# Dashboard_rev5.net
KiCad netlist of a schematic drawn in EAGLE
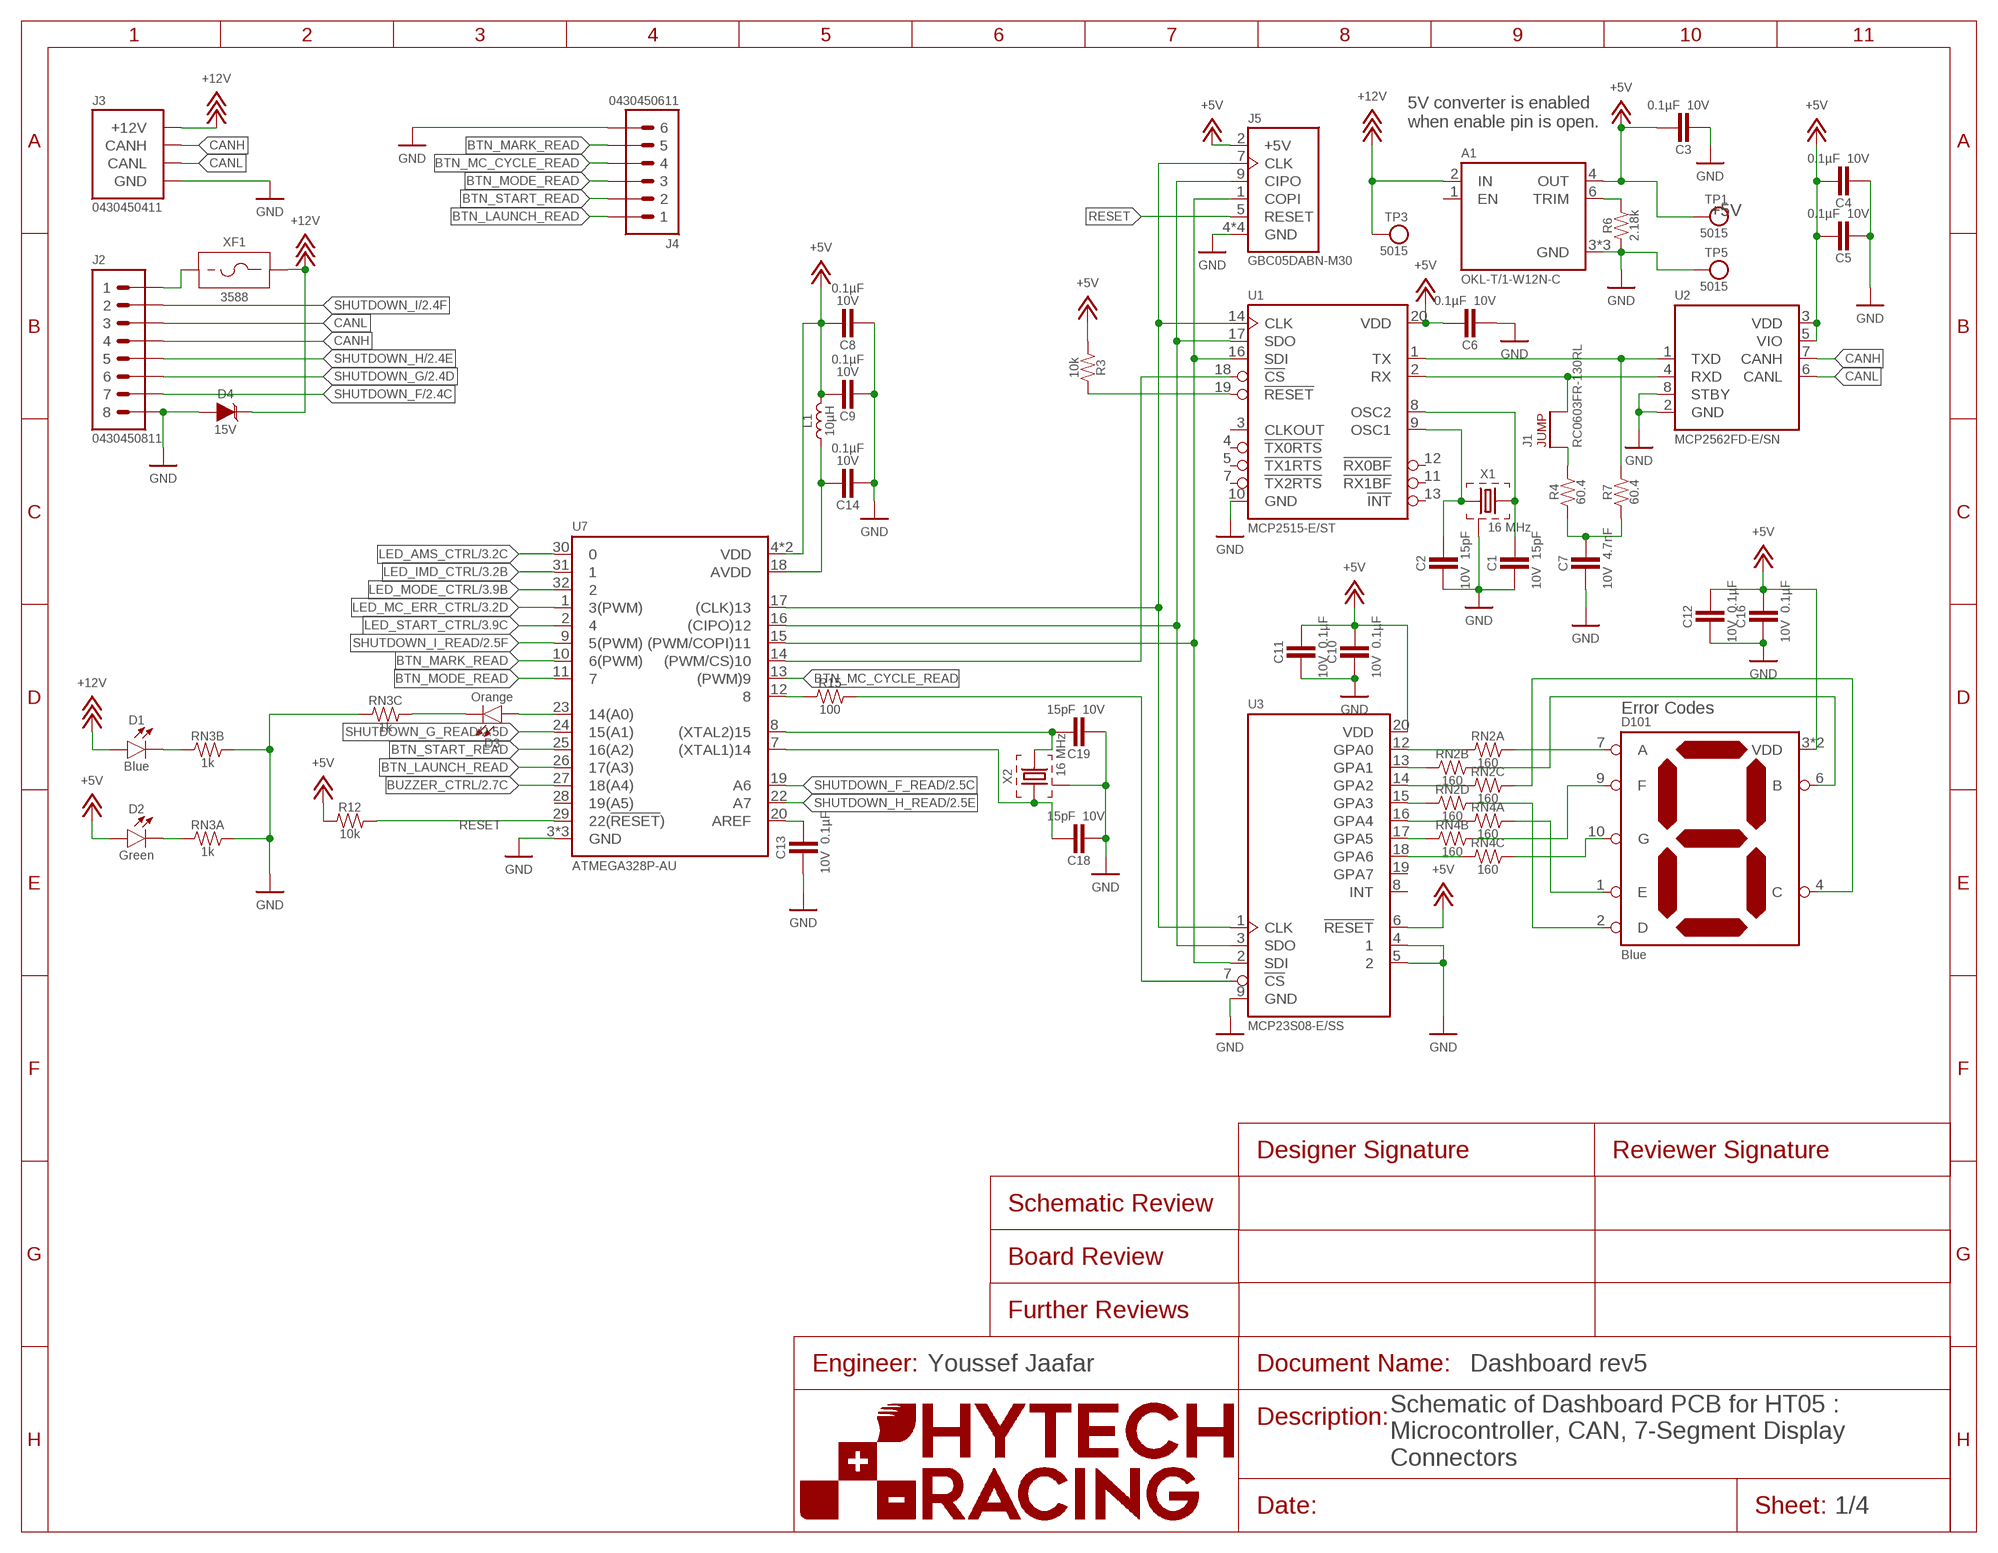
[diagram p0: schematic, sheet 1]
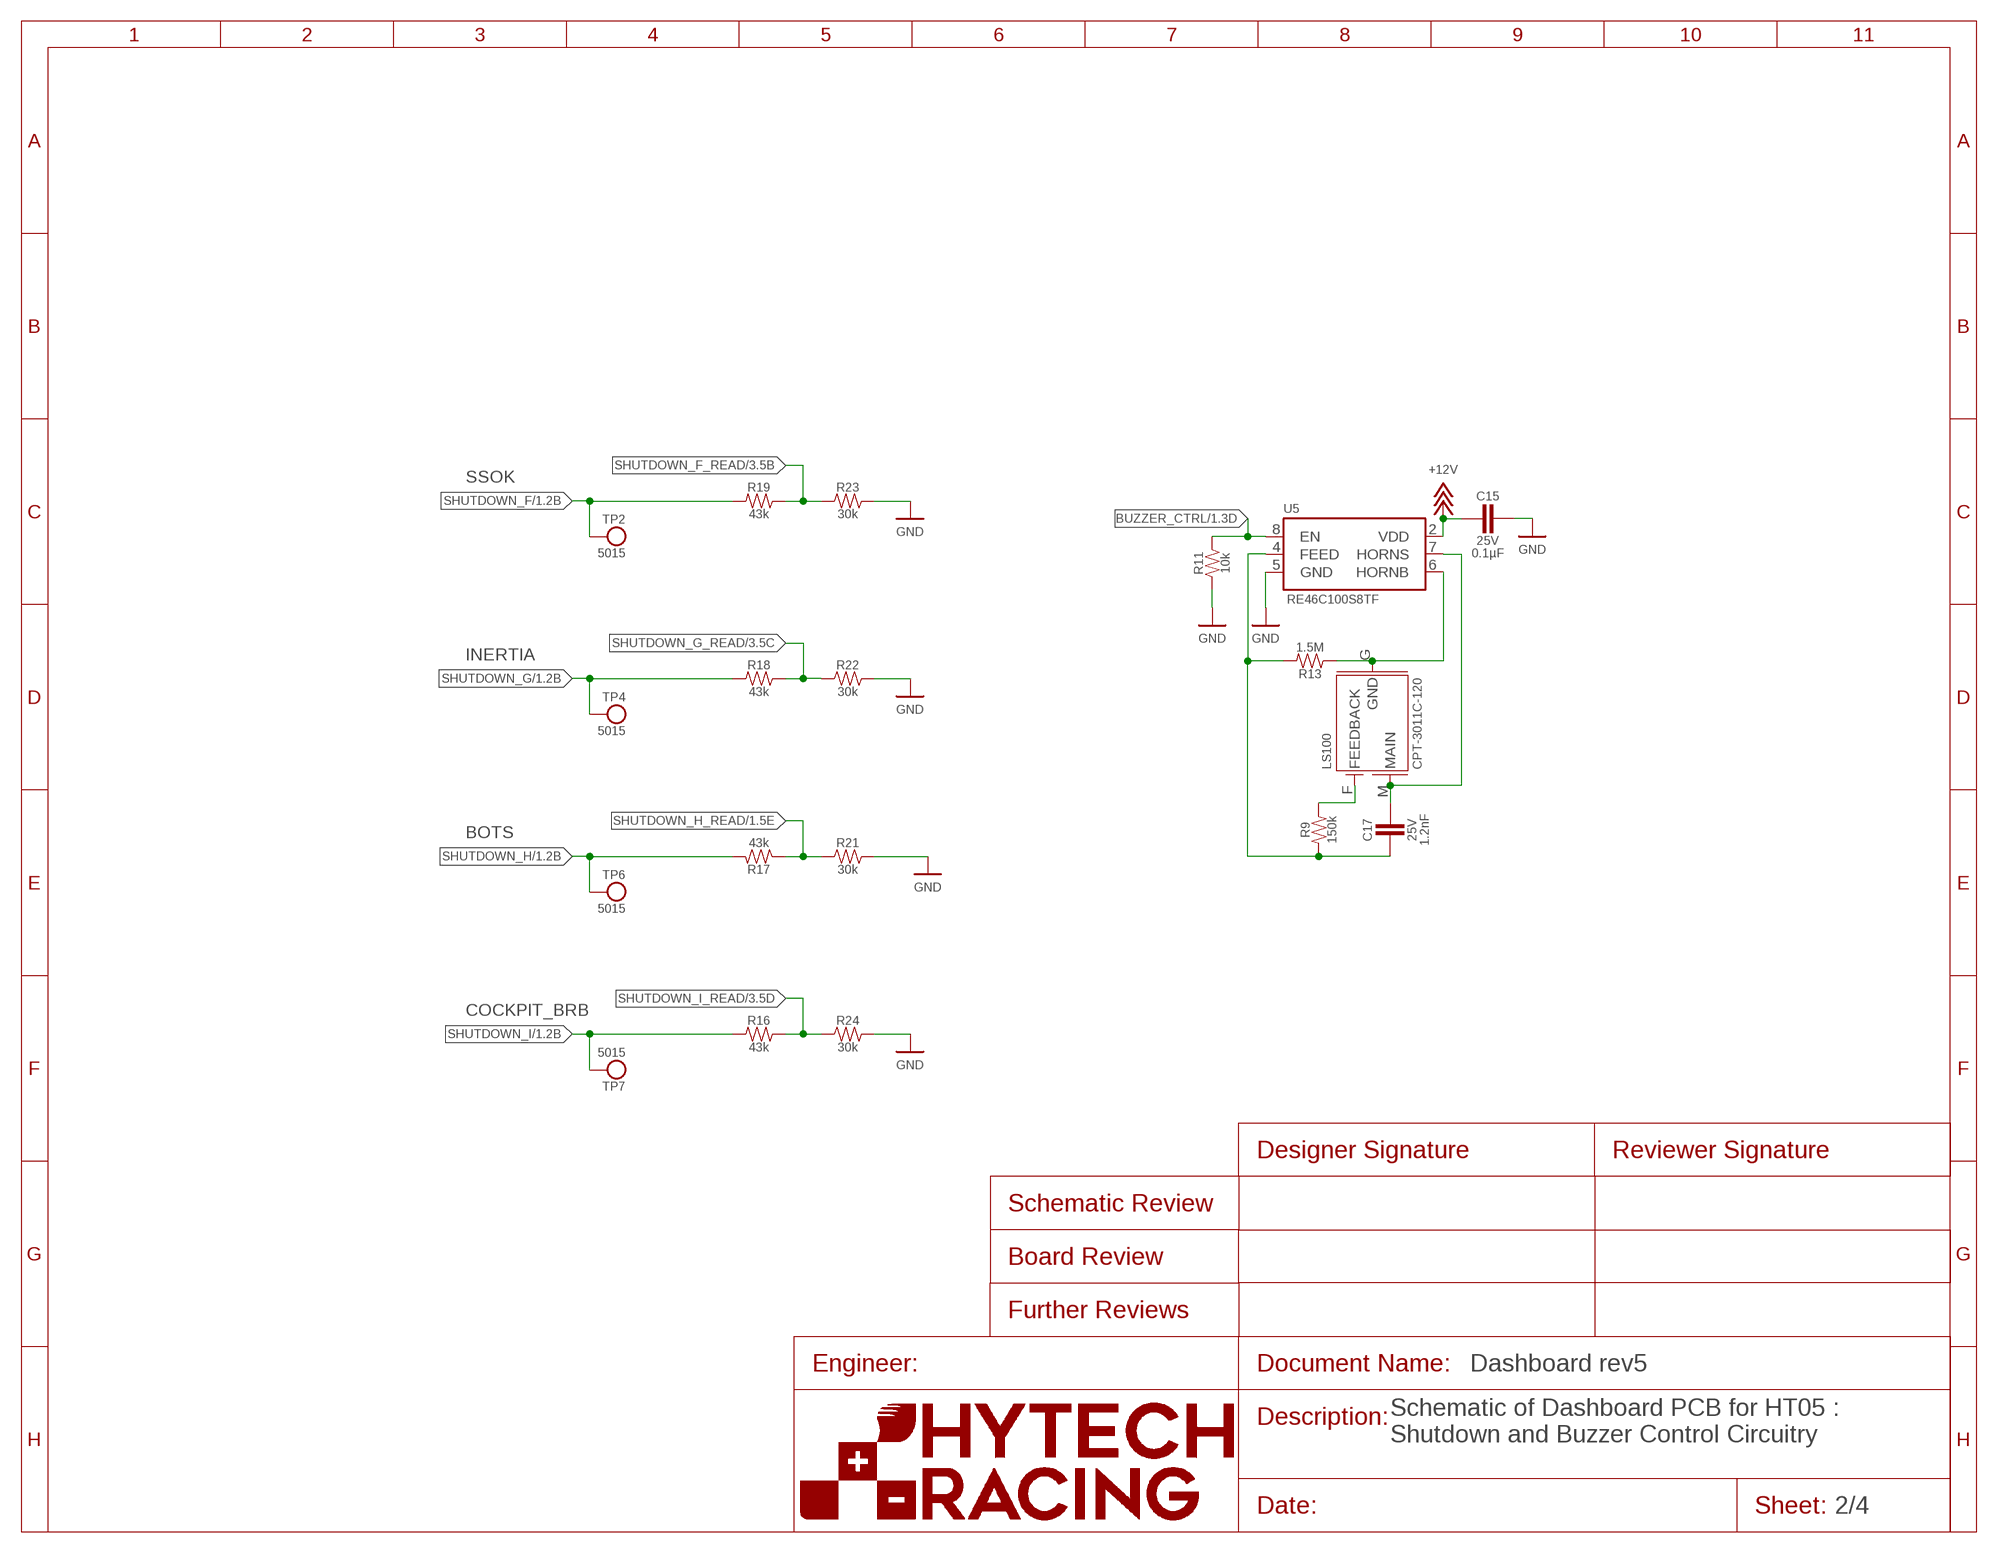
[diagram p1: schematic, sheet 2]
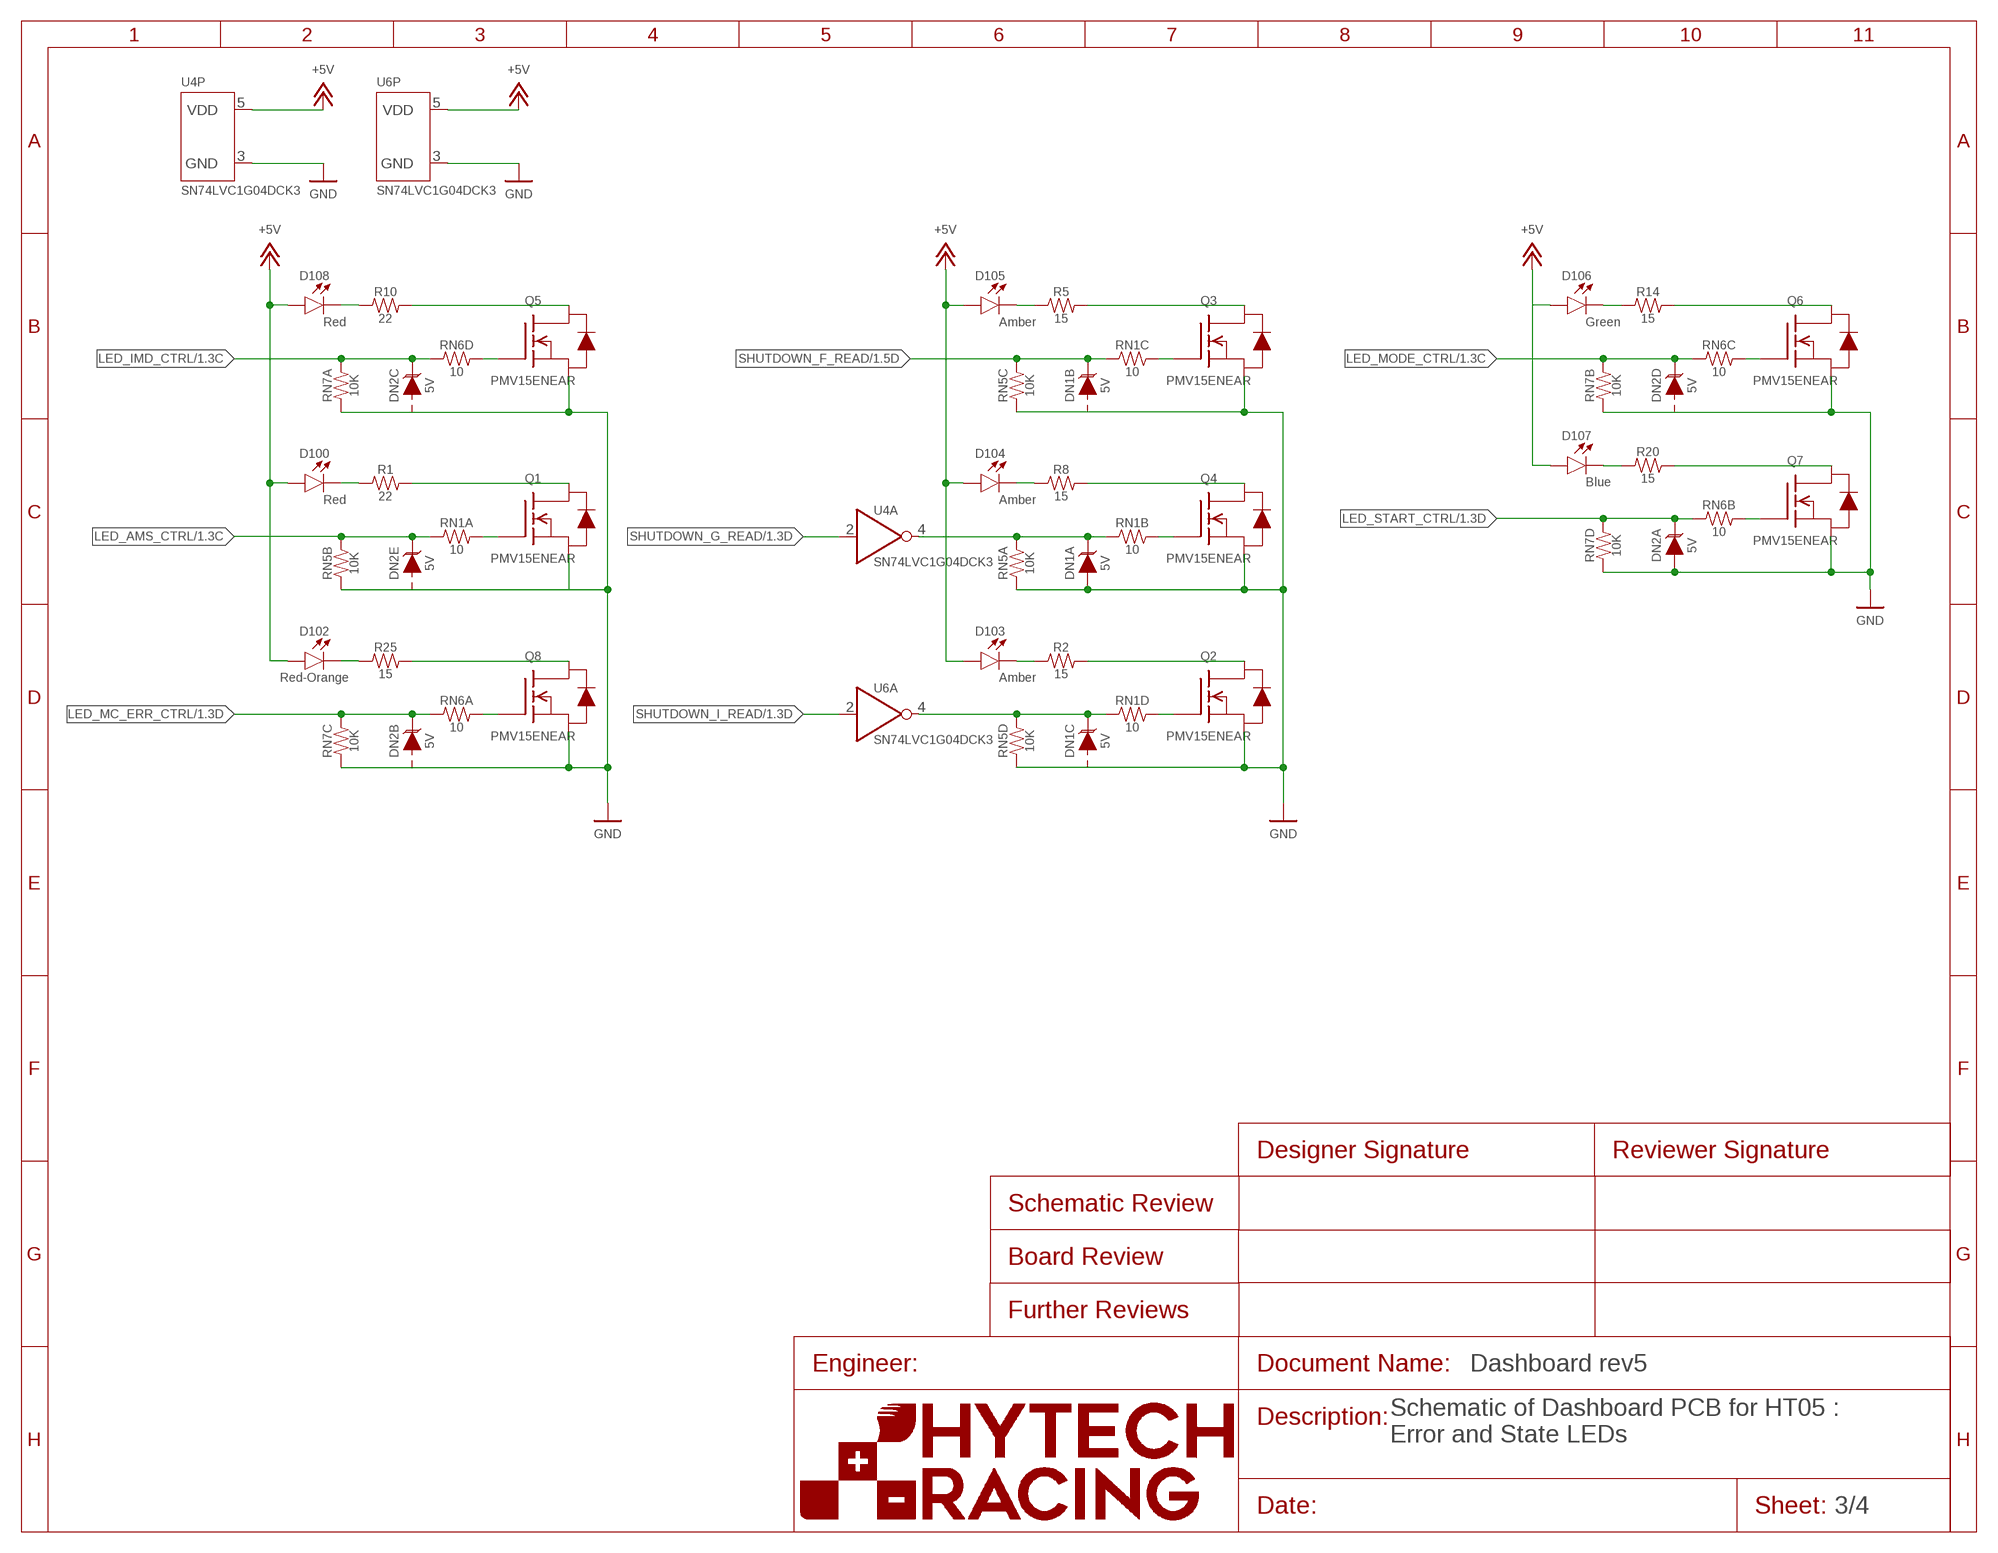
[diagram p2: schematic, sheet 3]
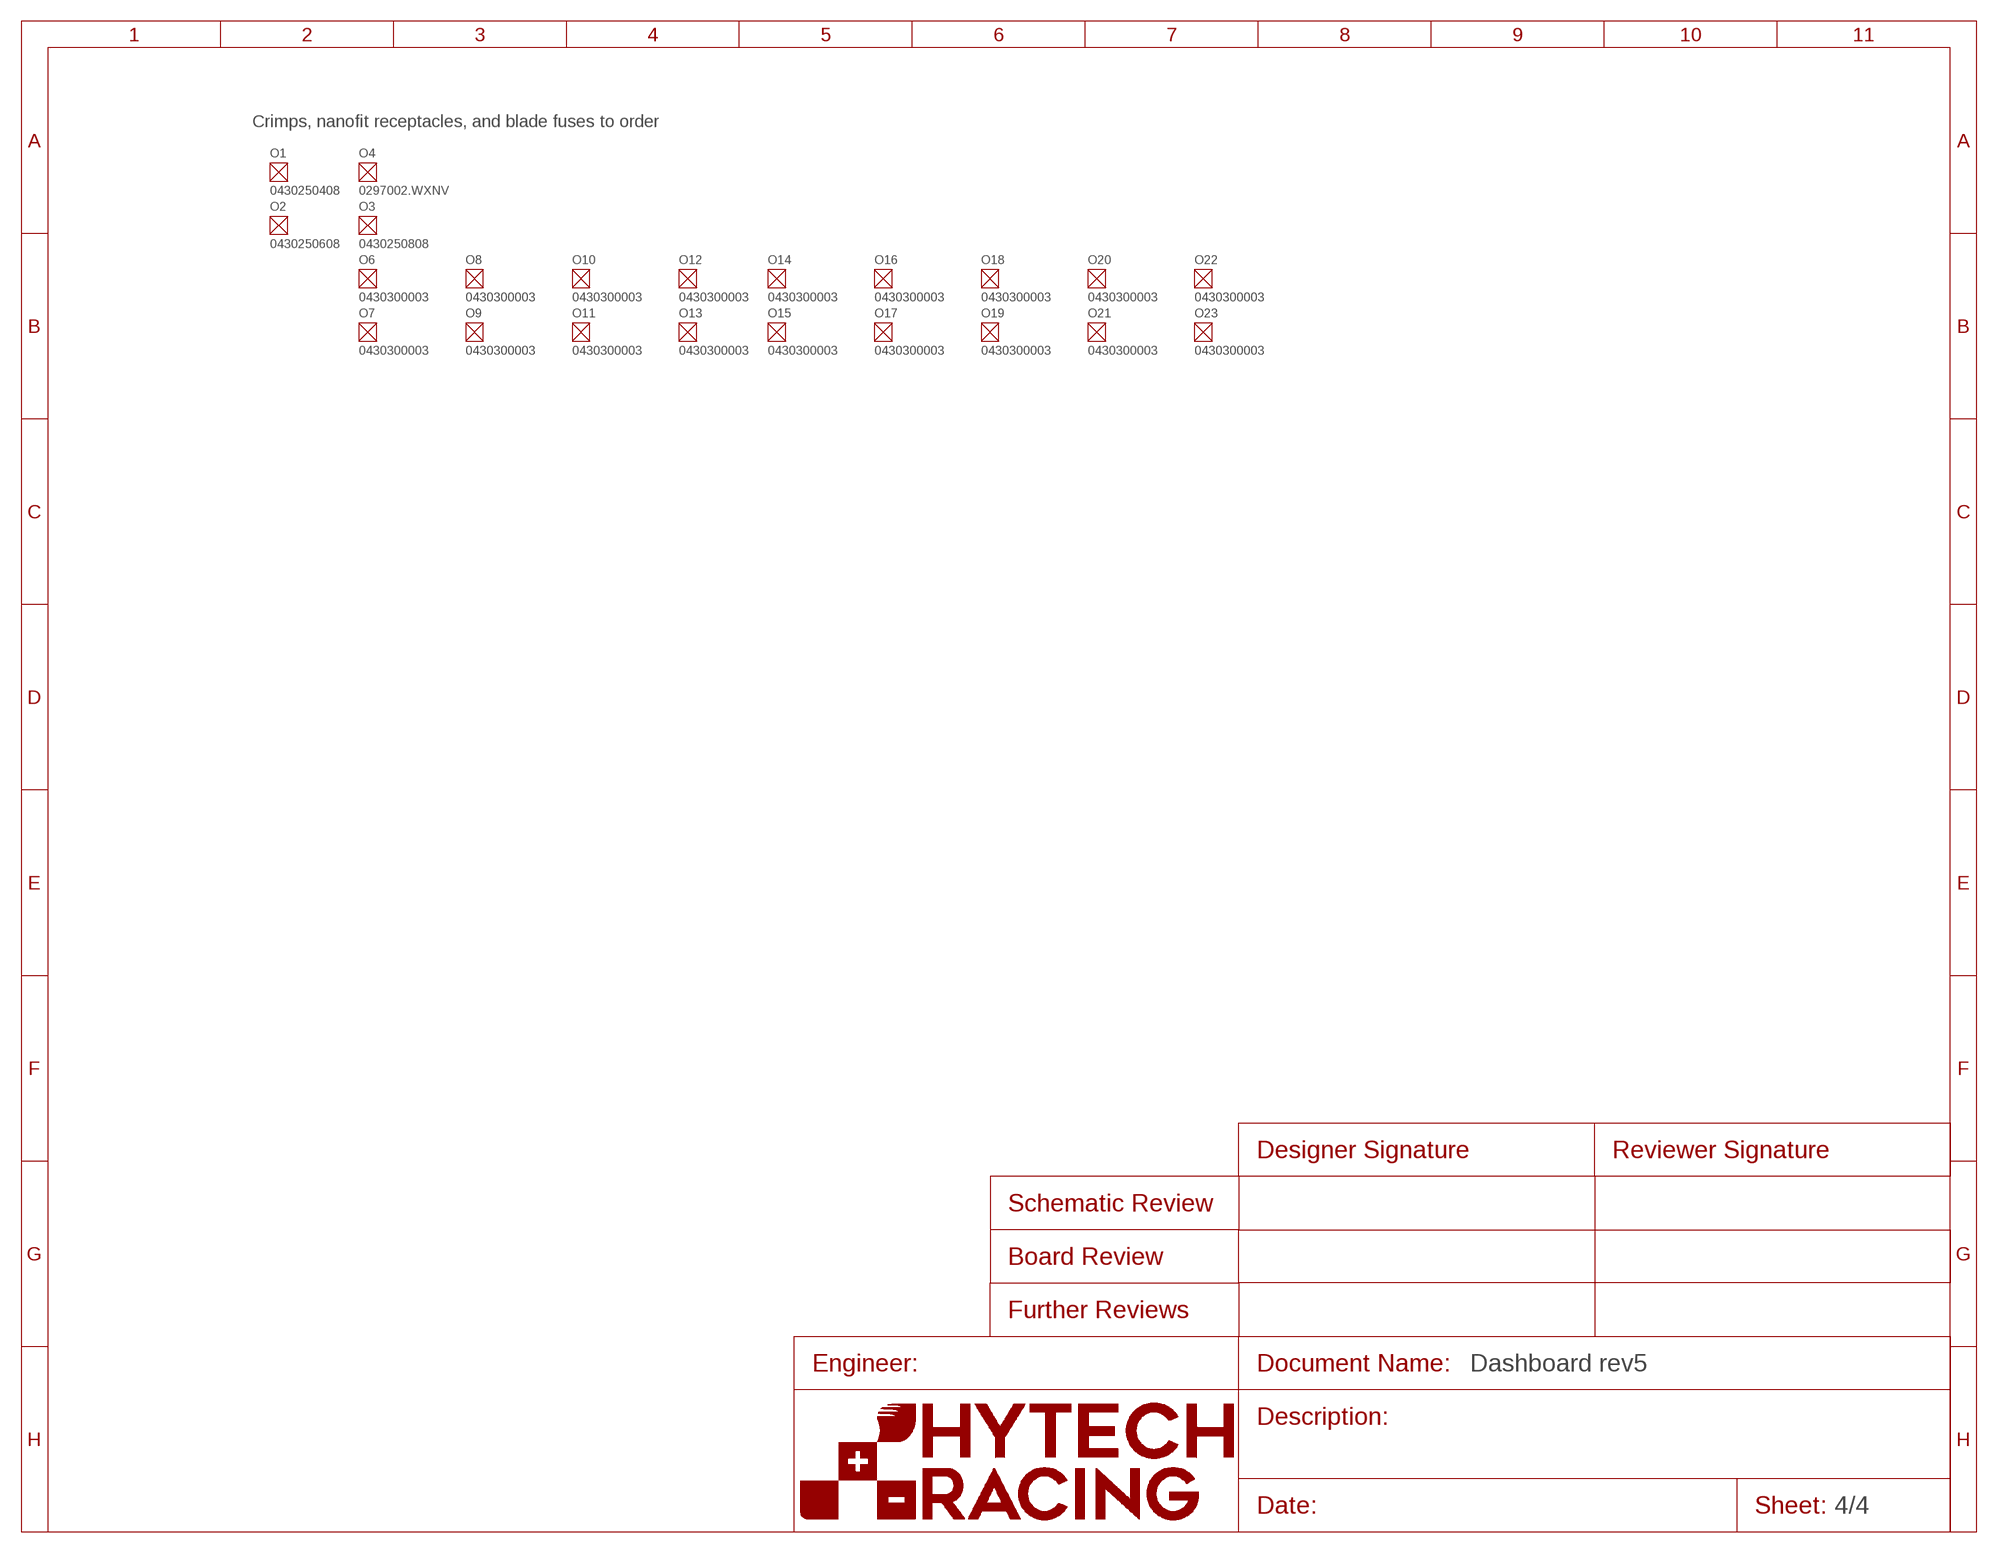
[diagram p3: schematic, sheet 4]

(export (version "E")
  (design (tool "Eeschema 10.0.6"))
  (components
    (comp (ref "D100")
      (value "LED_2835_RED")
      (footprint "eagle-import:2835-LED")
      (fields
        (field (name "COLOR") "Red")
        (field (name "MANUFACTURER") "Lumileds")
        (field (name "MPN") "L128-RED1003500000")
      )
      (libsource (lib "eagle-import") (part "LED_?_2835RED"))
    )
    (comp (ref "D102")
      (value "LED_2835_RED-ORANGE")
      (footprint "eagle-import:2835-LED")
      (fields
        (field (name "COLOR") "Red-Orange")
        (field (name "MANUFACTURER") "Lumileds")
        (field (name "MPN") "L128-RNG1003500000 ")
      )
      (libsource (lib "eagle-import") (part "LED_?_2835RED-ORANGE"))
    )
    (comp (ref "D103")
      (value "LED_2835_AMBER")
      (footprint "eagle-import:2835-LED")
      (fields
        (field (name "COLOR") "Amber")
        (field (name "MANUFACTURER") "Lumileds")
        (field (name "MPN") "L128-PCA1003500000")
      )
      (libsource (lib "eagle-import") (part "LED_?_2835AMBER"))
    )
    (comp (ref "D104")
      (value "LED_2835_AMBER")
      (footprint "eagle-import:2835-LED")
      (fields
        (field (name "COLOR") "Amber")
        (field (name "MANUFACTURER") "Lumileds")
        (field (name "MPN") "L128-PCA1003500000")
      )
      (libsource (lib "eagle-import") (part "LED_?_2835AMBER"))
    )
    (comp (ref "D105")
      (value "LED_2835_AMBER")
      (footprint "eagle-import:2835-LED")
      (fields
        (field (name "COLOR") "Amber")
        (field (name "MANUFACTURER") "Lumileds")
        (field (name "MPN") "L128-PCA1003500000")
      )
      (libsource (lib "eagle-import") (part "LED_?_2835AMBER"))
    )
    (comp (ref "D106")
      (value "LED_2835_GREEN")
      (footprint "eagle-import:2835-LED")
      (fields
        (field (name "COLOR") "Green")
        (field (name "MANUFACTURER") "Lumileds")
        (field (name "MPN") "L128-GRN1003500000")
      )
      (libsource (lib "eagle-import") (part "LED_?_2835GREEN"))
    )
    (comp (ref "D107")
      (value "LED_2835_BLUE")
      (footprint "eagle-import:2835-LED")
      (fields
        (field (name "COLOR") "Blue")
        (field (name "MANUFACTURER") "Lumileds")
        (field (name "MPN") "L128-BLU1003500000")
      )
      (libsource (lib "eagle-import") (part "LED_?_2835BLUE"))
    )
    (comp (ref "D108")
      (value "LED_2835_RED")
      (footprint "eagle-import:2835-LED")
      (fields
        (field (name "COLOR") "Red")
        (field (name "MANUFACTURER") "Lumileds")
        (field (name "MPN") "L128-RED1003500000")
      )
      (libsource (lib "eagle-import") (part "LED_?_2835RED"))
    )
    (comp (ref "DN1")
      (value "TVS_ARRAY_5V")
      (footprint "eagle-import:SOT-363")
      (fields
        (field (name "MANUFACTURER") "Vishay General Semiconductor - Diodes Division")
        (field (name "MPN") "VESD05A5-06G-G3-08")
        (field (name "VOLTAGE") "5V")
      )
      (libsource (lib "eagle-import") (part "TVS_ARRAY_5V"))
    )
    (comp (ref "DN2")
      (value "TVS_ARRAY_5V")
      (footprint "eagle-import:SOT-363")
      (fields
        (field (name "MANUFACTURER") "Vishay General Semiconductor - Diodes Division")
        (field (name "MPN") "VESD05A5-06G-G3-08")
        (field (name "VOLTAGE") "5V")
      )
      (libsource (lib "eagle-import") (part "TVS_ARRAY_5V"))
    )
    (comp (ref "Q1")
      (value "TRANSISTOR_N_MOS__PMV15ENEA")
      (footprint "eagle-import:SOT-23")
      (fields (field (name "MANUFACTURER") "Nexperia USA Inc.") (field (name "MPN") "PMV15ENEAR"))
      (libsource (lib "eagle-import") (part "TRANSISTOR_N_MOS_?_PMV15ENEA"))
    )
    (comp (ref "Q2")
      (value "TRANSISTOR_N_MOS__PMV15ENEA")
      (footprint "eagle-import:SOT-23")
      (fields (field (name "MANUFACTURER") "Nexperia USA Inc.") (field (name "MPN") "PMV15ENEAR"))
      (libsource (lib "eagle-import") (part "TRANSISTOR_N_MOS_?_PMV15ENEA"))
    )
    (comp (ref "Q3")
      (value "TRANSISTOR_N_MOS__PMV15ENEA")
      (footprint "eagle-import:SOT-23")
      (fields (field (name "MANUFACTURER") "Nexperia USA Inc.") (field (name "MPN") "PMV15ENEAR"))
      (libsource (lib "eagle-import") (part "TRANSISTOR_N_MOS_?_PMV15ENEA"))
    )
    (comp (ref "Q4")
      (value "TRANSISTOR_N_MOS__PMV15ENEA")
      (footprint "eagle-import:SOT-23")
      (fields (field (name "MANUFACTURER") "Nexperia USA Inc.") (field (name "MPN") "PMV15ENEAR"))
      (libsource (lib "eagle-import") (part "TRANSISTOR_N_MOS_?_PMV15ENEA"))
    )
    (comp (ref "Q5")
      (value "TRANSISTOR_N_MOS__PMV15ENEA")
      (footprint "eagle-import:SOT-23")
      (fields (field (name "MANUFACTURER") "Nexperia USA Inc.") (field (name "MPN") "PMV15ENEAR"))
      (libsource (lib "eagle-import") (part "TRANSISTOR_N_MOS_?_PMV15ENEA"))
    )
    (comp (ref "Q6")
      (value "TRANSISTOR_N_MOS__PMV15ENEA")
      (footprint "eagle-import:SOT-23")
      (fields (field (name "MANUFACTURER") "Nexperia USA Inc.") (field (name "MPN") "PMV15ENEAR"))
      (libsource (lib "eagle-import") (part "TRANSISTOR_N_MOS_?_PMV15ENEA"))
    )
    (comp (ref "Q7")
      (value "TRANSISTOR_N_MOS__PMV15ENEA")
      (footprint "eagle-import:SOT-23")
      (fields (field (name "MANUFACTURER") "Nexperia USA Inc.") (field (name "MPN") "PMV15ENEAR"))
      (libsource (lib "eagle-import") (part "TRANSISTOR_N_MOS_?_PMV15ENEA"))
    )
    (comp (ref "Q8")
      (value "TRANSISTOR_N_MOS__PMV15ENEA")
      (footprint "eagle-import:SOT-23")
      (fields (field (name "MANUFACTURER") "Nexperia USA Inc.") (field (name "MPN") "PMV15ENEAR"))
      (libsource (lib "eagle-import") (part "TRANSISTOR_N_MOS_?_PMV15ENEA"))
    )
    (comp (ref "R1")
      (value "RESISTOR_0805_22")
      (footprint "eagle-import:0805-RES")
      (fields
        (field (name "MANUFACTURER") "Panasonic Electronic Components")
        (field (name "MPN") "ERJ-P06F22R0V")
        (field (name "POWER") "0.5W")
        (field (name "RESISTANCE") "22")
      )
      (libsource (lib "eagle-import") (part "RESISTOR_?_080522"))
    )
    (comp (ref "R2")
      (value "RESISTOR_0603_15")
      (footprint "eagle-import:0603-RES")
      (fields
        (field (name "MANUFACTURER") "Vishay Dale")
        (field (name "MPN") "CRCW060315R0FKEAHP")
        (field (name "POWER") "0.33W")
        (field (name "RESISTANCE") "15")
      )
      (libsource (lib "eagle-import") (part "RESISTOR_?_060315"))
    )
    (comp (ref "R5")
      (value "RESISTOR_0603_15")
      (footprint "eagle-import:0603-RES")
      (fields
        (field (name "MANUFACTURER") "Vishay Dale")
        (field (name "MPN") "CRCW060315R0FKEAHP")
        (field (name "POWER") "0.33W")
        (field (name "RESISTANCE") "15")
      )
      (libsource (lib "eagle-import") (part "RESISTOR_?_060315"))
    )
    (comp (ref "R8")
      (value "RESISTOR_0603_15")
      (footprint "eagle-import:0603-RES")
      (fields
        (field (name "MANUFACTURER") "Vishay Dale")
        (field (name "MPN") "CRCW060315R0FKEAHP")
        (field (name "POWER") "0.33W")
        (field (name "RESISTANCE") "15")
      )
      (libsource (lib "eagle-import") (part "RESISTOR_?_060315"))
    )
    (comp (ref "R10")
      (value "RESISTOR_0805_22")
      (footprint "eagle-import:0805-RES")
      (fields
        (field (name "MANUFACTURER") "Panasonic Electronic Components")
        (field (name "MPN") "ERJ-P06F22R0V")
        (field (name "POWER") "0.5W")
        (field (name "RESISTANCE") "22")
      )
      (libsource (lib "eagle-import") (part "RESISTOR_?_080522"))
    )
    (comp (ref "R14")
      (value "RESISTOR_0603_15")
      (footprint "eagle-import:0603-RES")
      (fields
        (field (name "MANUFACTURER") "Vishay Dale")
        (field (name "MPN") "CRCW060315R0FKEAHP")
        (field (name "POWER") "0.33W")
        (field (name "RESISTANCE") "15")
      )
      (libsource (lib "eagle-import") (part "RESISTOR_?_060315"))
    )
    (comp (ref "R20")
      (value "RESISTOR_0603_15")
      (footprint "eagle-import:0603-RES")
      (fields
        (field (name "MANUFACTURER") "Vishay Dale")
        (field (name "MPN") "CRCW060315R0FKEAHP")
        (field (name "POWER") "0.33W")
        (field (name "RESISTANCE") "15")
      )
      (libsource (lib "eagle-import") (part "RESISTOR_?_060315"))
    )
    (comp (ref "R25")
      (value "RESISTOR_0603_15")
      (footprint "eagle-import:0603-RES")
      (fields
        (field (name "MANUFACTURER") "Vishay Dale")
        (field (name "MPN") "CRCW060315R0FKEAHP")
        (field (name "POWER") "0.33W")
        (field (name "RESISTANCE") "15")
      )
      (libsource (lib "eagle-import") (part "RESISTOR_?_060315"))
    )
    (comp (ref "RN1")
      (value "RESISTOR_NETWORK_4_10")
      (footprint "eagle-import:1206-RES-ARRAY")
      (fields
        (field (name "MANUFACTURER") "Bourns Inc.")
        (field (name "MPN") "CAT16-100J4LF")
        (field (name "POWER") "1/16W")
        (field (name "RESISTANCE") "10")
      )
      (libsource (lib "eagle-import") (part "RESISTOR_NETWORK_4_10"))
    )
    (comp (ref "RN5")
      (value "RESISTOR_NETWORK_4_10K")
      (footprint "eagle-import:1206-RES-ARRAY")
      (fields
        (field (name "MANUFACTURER") "Yageo")
        (field (name "MPN") "TC164-FR-0710KL")
        (field (name "POWER") "1/16W")
        (field (name "RESISTANCE") "10K")
      )
      (libsource (lib "eagle-import") (part "RESISTOR_NETWORK_4_10K"))
    )
    (comp (ref "RN6")
      (value "RESISTOR_NETWORK_4_10")
      (footprint "eagle-import:1206-RES-ARRAY")
      (fields
        (field (name "MANUFACTURER") "Bourns Inc.")
        (field (name "MPN") "CAT16-100J4LF")
        (field (name "POWER") "1/16W")
        (field (name "RESISTANCE") "10")
      )
      (libsource (lib "eagle-import") (part "RESISTOR_NETWORK_4_10"))
    )
    (comp (ref "RN7")
      (value "RESISTOR_NETWORK_4_10K")
      (footprint "eagle-import:1206-RES-ARRAY")
      (fields
        (field (name "MANUFACTURER") "Yageo")
        (field (name "MPN") "TC164-FR-0710KL")
        (field (name "POWER") "1/16W")
        (field (name "RESISTANCE") "10K")
      )
      (libsource (lib "eagle-import") (part "RESISTOR_NETWORK_4_10K"))
    )
    (comp (ref "U4")
      (value "LOGICGATE_INVERTER_DCK3")
      (footprint "eagle-import:SC-70-5")
      (fields (field (name "MANUFACTURER") "Texas Instruments") (field (name "MPN") "SN74LVC1G04DCK3"))
      (libsource (lib "eagle-import") (part "LOGICGATE_INVERTER_DCK3"))
    )
    (comp (ref "U6")
      (value "LOGICGATE_INVERTER_DCK3")
      (footprint "eagle-import:SC-70-5")
      (fields (field (name "MANUFACTURER") "Texas Instruments") (field (name "MPN") "SN74LVC1G04DCK3"))
      (libsource (lib "eagle-import") (part "LOGICGATE_INVERTER_DCK3"))
    )
    (comp (ref "C15")
      (value "CAPACITOR_0603_25V_0.1UF")
      (footprint "eagle-import:0603-CAP")
      (fields
        (field (name "CAPACITANCE") "0.1µF")
        (field (name "MANUFACTURER") "Samsung Electro-Mechanics")
        (field (name "MPN") "CL10B104KA8NNNC")
        (field (name "TOLERANCE") "10%")
        (field (name "VOLTAGE") "25V")
      )
      (libsource (lib "eagle-import") (part "CAPACITOR_?_060325V_0.1UF"))
    )
    (comp (ref "C17")
      (value "CAPACITOR_0603_25V_1.2NF")
      (footprint "eagle-import:0603-CAP")
      (fields
        (field (name "CAPACITANCE") "1.2nF")
        (field (name "MANUFACTURER") "YAGEO")
        (field (name "MPN") "CC0603KRX7R8BB122")
        (field (name "TOLERANCE") "10%")
        (field (name "VOLTAGE") "25V")
      )
      (libsource (lib "eagle-import") (part "CAPACITOR_?_060325V_1.2NF"))
    )
    (comp (ref "LS100")
      (value "BUZZER_3_PIN_CPT-3011C-120")
      (footprint "eagle-import:CPT-3011C-120")
      (fields
        (field (name "MANUFACTURER") "CUI Devices")
        (field (name "MPN") "CPT-3011C-120")
        (field (name "VOLTAGE") "12V")
      )
      (libsource (lib "eagle-import") (part "BUZZER_3_PIN_CPT-3011C-120"))
    )
    (comp (ref "R9")
      (value "RESISTOR_0603_150K")
      (footprint "eagle-import:0603-RES")
      (fields
        (field (name "MANUFACTURER") "Panasonic Electronic Components")
        (field (name "MPN") "ERA-3AEB154V")
        (field (name "POWER") "0.1W")
        (field (name "RESISTANCE") "150k")
      )
      (libsource (lib "eagle-import") (part "RESISTOR_?_0603150K"))
    )
    (comp (ref "R11")
      (value "RESISTOR_0603_10K")
      (footprint "eagle-import:0603-RES")
      (fields
        (field (name "MANUFACTURER") "Yageo")
        (field (name "MPN") "RC0603FR-0710KL")
        (field (name "POWER") "0.1W")
        (field (name "RESISTANCE") "10k")
      )
      (libsource (lib "eagle-import") (part "RESISTOR_?_060310K"))
    )
    (comp (ref "R13")
      (value "RESISTOR_0603_1.5M")
      (footprint "eagle-import:0603-RES")
      (fields
        (field (name "MANUFACTURER") "Yageo")
        (field (name "MPN") "RC0603FR-071M5L")
        (field (name "POWER") "0.1W")
        (field (name "RESISTANCE") "1.5M")
      )
      (libsource (lib "eagle-import") (part "RESISTOR_?_06031.5M"))
    )
    (comp (ref "R16")
      (value "RESISTOR_0603_43K")
      (footprint "eagle-import:0603-RES")
      (fields
        (field (name "MANUFACTURER") "Yageo")
        (field (name "MPN") "RC0603FR-0743KL")
        (field (name "POWER") "0.1W")
        (field (name "RESISTANCE") "43k")
      )
      (libsource (lib "eagle-import") (part "RESISTOR_?_060343K"))
    )
    (comp (ref "R17")
      (value "RESISTOR_0603_43K")
      (footprint "eagle-import:0603-RES")
      (fields
        (field (name "MANUFACTURER") "Yageo")
        (field (name "MPN") "RC0603FR-0743KL")
        (field (name "POWER") "0.1W")
        (field (name "RESISTANCE") "43k")
      )
      (libsource (lib "eagle-import") (part "RESISTOR_?_060343K"))
    )
    (comp (ref "R18")
      (value "RESISTOR_0603_43K")
      (footprint "eagle-import:0603-RES")
      (fields
        (field (name "MANUFACTURER") "Yageo")
        (field (name "MPN") "RC0603FR-0743KL")
        (field (name "POWER") "0.1W")
        (field (name "RESISTANCE") "43k")
      )
      (libsource (lib "eagle-import") (part "RESISTOR_?_060343K"))
    )
    (comp (ref "R19")
      (value "RESISTOR_0603_43K")
      (footprint "eagle-import:0603-RES")
      (fields
        (field (name "MANUFACTURER") "Yageo")
        (field (name "MPN") "RC0603FR-0743KL")
        (field (name "POWER") "0.1W")
        (field (name "RESISTANCE") "43k")
      )
      (libsource (lib "eagle-import") (part "RESISTOR_?_060343K"))
    )
    (comp (ref "R21")
      (value "RESISTOR_0603_30K")
      (footprint "eagle-import:0603-RES")
      (fields
        (field (name "MANUFACTURER") "Panasonic Electronic Components")
        (field (name "MPN") "ERA-3ARB303V")
        (field (name "POWER") "0.1W")
        (field (name "RESISTANCE") "30k")
      )
      (libsource (lib "eagle-import") (part "RESISTOR_?_060330K"))
    )
    (comp (ref "R22")
      (value "RESISTOR_0603_30K")
      (footprint "eagle-import:0603-RES")
      (fields
        (field (name "MANUFACTURER") "Panasonic Electronic Components")
        (field (name "MPN") "ERA-3ARB303V")
        (field (name "POWER") "0.1W")
        (field (name "RESISTANCE") "30k")
      )
      (libsource (lib "eagle-import") (part "RESISTOR_?_060330K"))
    )
    (comp (ref "R23")
      (value "RESISTOR_0603_30K")
      (footprint "eagle-import:0603-RES")
      (fields
        (field (name "MANUFACTURER") "Panasonic Electronic Components")
        (field (name "MPN") "ERA-3ARB303V")
        (field (name "POWER") "0.1W")
        (field (name "RESISTANCE") "30k")
      )
      (libsource (lib "eagle-import") (part "RESISTOR_?_060330K"))
    )
    (comp (ref "R24")
      (value "RESISTOR_0603_30K")
      (footprint "eagle-import:0603-RES")
      (fields
        (field (name "MANUFACTURER") "Panasonic Electronic Components")
        (field (name "MPN") "ERA-3ARB303V")
        (field (name "POWER") "0.1W")
        (field (name "RESISTANCE") "30k")
      )
      (libsource (lib "eagle-import") (part "RESISTOR_?_060330K"))
    )
    (comp (ref "TP2")
      (value "TEST_POINT")
      (footprint "eagle-import:5015")
      (fields (field (name "MPN") "5015") (field (name "MANUFACTURER") "Keystone Electronics"))
      (libsource (lib "eagle-import") (part "TEST_POINT"))
    )
    (comp (ref "TP4")
      (value "TEST_POINT")
      (footprint "eagle-import:5015")
      (fields (field (name "MPN") "5015") (field (name "MANUFACTURER") "Keystone Electronics"))
      (libsource (lib "eagle-import") (part "TEST_POINT"))
    )
    (comp (ref "TP6")
      (value "TEST_POINT")
      (footprint "eagle-import:5015")
      (fields (field (name "MPN") "5015") (field (name "MANUFACTURER") "Keystone Electronics"))
      (libsource (lib "eagle-import") (part "TEST_POINT"))
    )
    (comp (ref "TP7")
      (value "TEST_POINT")
      (footprint "eagle-import:5015")
      (fields (field (name "MPN") "5015") (field (name "MANUFACTURER") "Keystone Electronics"))
      (libsource (lib "eagle-import") (part "TEST_POINT"))
    )
    (comp (ref "U5")
      (value "RE46C100")
      (footprint "eagle-import:SOIC-08(NARROW,0.15_)")
      (fields (field (name "MPN") " RE46C100S8TF") (field (name "MANUFACTURER") "Microchip Technology"))
      (libsource (lib "eagle-import") (part "RE46C100"))
    )
    (comp (ref "A1")
      (value "OKL-T/1-W12N-COKL")
      (footprint "eagle-import:OKL-T_1-W12")
      (fields
        (field (name "MANUFACTURER") "Murata Power Solutions Inc.")
        (field (name "MPN") "OKL-T/1-W12N-C")
      )
      (libsource (lib "eagle-import") (part "OKL-OKLT/1-W12N-C"))
    )
    (comp (ref "C1")
      (value "CAPACITOR_0603_10V_15PF")
      (footprint "eagle-import:0603-CAP")
      (fields
        (field (name "CAPACITANCE") "15pF")
        (field (name "MANUFACTURER") "Vishay Vitramon")
        (field (name "MPN") "VJ0603A150FXQPW1BC")
        (field (name "TOLERANCE") "1%")
        (field (name "VOLTAGE") "10V")
      )
      (libsource (lib "eagle-import") (part "CAPACITOR_?_060310V_15PF"))
    )
    (comp (ref "C2")
      (value "CAPACITOR_0603_10V_15PF")
      (footprint "eagle-import:0603-CAP")
      (fields
        (field (name "CAPACITANCE") "15pF")
        (field (name "MANUFACTURER") "Vishay Vitramon")
        (field (name "MPN") "VJ0603A150FXQPW1BC")
        (field (name "TOLERANCE") "1%")
        (field (name "VOLTAGE") "10V")
      )
      (libsource (lib "eagle-import") (part "CAPACITOR_?_060310V_15PF"))
    )
    (comp (ref "C3")
      (value "CAPACITOR_0603_10V_0.1UF")
      (footprint "eagle-import:0603-CAP")
      (fields
        (field (name "CAPACITANCE") "0.1µF")
        (field (name "MANUFACTURER") "Vishay Vitramon")
        (field (name "MPN") "VJ0603Y104JXQPW1BC")
        (field (name "TOLERANCE") "5%")
        (field (name "VOLTAGE") "10V")
      )
      (libsource (lib "eagle-import") (part "CAPACITOR_?_060310V_0.1UF"))
    )
    (comp (ref "C4")
      (value "CAPACITOR_0603_10V_0.1UF")
      (footprint "eagle-import:0603-CAP")
      (fields
        (field (name "CAPACITANCE") "0.1µF")
        (field (name "MANUFACTURER") "Vishay Vitramon")
        (field (name "MPN") "VJ0603Y104JXQPW1BC")
        (field (name "TOLERANCE") "5%")
        (field (name "VOLTAGE") "10V")
      )
      (libsource (lib "eagle-import") (part "CAPACITOR_?_060310V_0.1UF"))
    )
    (comp (ref "C5")
      (value "CAPACITOR_0603_10V_0.1UF")
      (footprint "eagle-import:0603-CAP")
      (fields
        (field (name "CAPACITANCE") "0.1µF")
        (field (name "MANUFACTURER") "Vishay Vitramon")
        (field (name "MPN") "VJ0603Y104JXQPW1BC")
        (field (name "TOLERANCE") "5%")
        (field (name "VOLTAGE") "10V")
      )
      (libsource (lib "eagle-import") (part "CAPACITOR_?_060310V_0.1UF"))
    )
    (comp (ref "C6")
      (value "CAPACITOR_0603_10V_0.1UF")
      (footprint "eagle-import:0603-CAP")
      (fields
        (field (name "CAPACITANCE") "0.1µF")
        (field (name "MANUFACTURER") "Vishay Vitramon")
        (field (name "MPN") "VJ0603Y104JXQPW1BC")
        (field (name "TOLERANCE") "5%")
        (field (name "VOLTAGE") "10V")
      )
      (libsource (lib "eagle-import") (part "CAPACITOR_?_060310V_0.1UF"))
    )
    (comp (ref "C7")
      (value "CAPACITOR_0603_10V_4.7NF")
      (footprint "eagle-import:0603-CAP")
      (fields
        (field (name "CAPACITANCE") "4.7nF")
        (field (name "MANUFACTURER") "Würth Elektronik")
        (field (name "MPN") "885012206012")
        (field (name "TOLERANCE") "10%")
        (field (name "VOLTAGE") "10V")
      )
      (libsource (lib "eagle-import") (part "CAPACITOR_?_060310V_4.7NF"))
    )
    (comp (ref "C8")
      (value "CAPACITOR_0603_10V_0.1UF")
      (footprint "eagle-import:0603-CAP")
      (fields
        (field (name "CAPACITANCE") "0.1µF")
        (field (name "MANUFACTURER") "Vishay Vitramon")
        (field (name "MPN") "VJ0603Y104JXQPW1BC")
        (field (name "TOLERANCE") "5%")
        (field (name "VOLTAGE") "10V")
      )
      (libsource (lib "eagle-import") (part "CAPACITOR_?_060310V_0.1UF"))
    )
    (comp (ref "C9")
      (value "CAPACITOR_0603_10V_0.1UF")
      (footprint "eagle-import:0603-CAP")
      (fields
        (field (name "CAPACITANCE") "0.1µF")
        (field (name "MANUFACTURER") "Vishay Vitramon")
        (field (name "MPN") "VJ0603Y104JXQPW1BC")
        (field (name "TOLERANCE") "5%")
        (field (name "VOLTAGE") "10V")
      )
      (libsource (lib "eagle-import") (part "CAPACITOR_?_060310V_0.1UF"))
    )
    (comp (ref "C10")
      (value "CAPACITOR_0603_10V_0.1UF")
      (footprint "eagle-import:0603-CAP")
      (fields
        (field (name "CAPACITANCE") "0.1µF")
        (field (name "MANUFACTURER") "Vishay Vitramon")
        (field (name "MPN") "VJ0603Y104JXQPW1BC")
        (field (name "TOLERANCE") "5%")
        (field (name "VOLTAGE") "10V")
      )
      (libsource (lib "eagle-import") (part "CAPACITOR_?_060310V_0.1UF"))
    )
    (comp (ref "C11")
      (value "CAPACITOR_0603_10V_0.1UF")
      (footprint "eagle-import:0603-CAP")
      (fields
        (field (name "CAPACITANCE") "0.1µF")
        (field (name "MANUFACTURER") "Vishay Vitramon")
        (field (name "MPN") "VJ0603Y104JXQPW1BC")
        (field (name "TOLERANCE") "5%")
        (field (name "VOLTAGE") "10V")
      )
      (libsource (lib "eagle-import") (part "CAPACITOR_?_060310V_0.1UF"))
    )
    (comp (ref "C12")
      (value "CAPACITOR_0603_10V_0.1UF")
      (footprint "eagle-import:0603-CAP")
      (fields
        (field (name "CAPACITANCE") "0.1µF")
        (field (name "MANUFACTURER") "Vishay Vitramon")
        (field (name "MPN") "VJ0603Y104JXQPW1BC")
        (field (name "TOLERANCE") "5%")
        (field (name "VOLTAGE") "10V")
      )
      (libsource (lib "eagle-import") (part "CAPACITOR_?_060310V_0.1UF"))
    )
    (comp (ref "C13")
      (value "CAPACITOR_0603_10V_0.1UF")
      (footprint "eagle-import:0603-CAP")
      (fields
        (field (name "CAPACITANCE") "0.1µF")
        (field (name "MANUFACTURER") "Vishay Vitramon")
        (field (name "MPN") "VJ0603Y104JXQPW1BC")
        (field (name "TOLERANCE") "5%")
        (field (name "VOLTAGE") "10V")
      )
      (libsource (lib "eagle-import") (part "CAPACITOR_?_060310V_0.1UF"))
    )
    (comp (ref "C14")
      (value "CAPACITOR_0603_10V_0.1UF")
      (footprint "eagle-import:0603-CAP")
      (fields
        (field (name "CAPACITANCE") "0.1µF")
        (field (name "MANUFACTURER") "Vishay Vitramon")
        (field (name "MPN") "VJ0603Y104JXQPW1BC")
        (field (name "TOLERANCE") "5%")
        (field (name "VOLTAGE") "10V")
      )
      (libsource (lib "eagle-import") (part "CAPACITOR_?_060310V_0.1UF"))
    )
    (comp (ref "C16")
      (value "CAPACITOR_0603_10V_0.1UF")
      (footprint "eagle-import:0603-CAP")
      (fields
        (field (name "CAPACITANCE") "0.1µF")
        (field (name "MANUFACTURER") "Vishay Vitramon")
        (field (name "MPN") "VJ0603Y104JXQPW1BC")
        (field (name "TOLERANCE") "5%")
        (field (name "VOLTAGE") "10V")
      )
      (libsource (lib "eagle-import") (part "CAPACITOR_?_060310V_0.1UF"))
    )
    (comp (ref "C18")
      (value "CAPACITOR_0603_10V_15PF")
      (footprint "eagle-import:0603-CAP")
      (fields
        (field (name "CAPACITANCE") "15pF")
        (field (name "MANUFACTURER") "Vishay Vitramon")
        (field (name "MPN") "VJ0603A150FXQPW1BC")
        (field (name "TOLERANCE") "1%")
        (field (name "VOLTAGE") "10V")
      )
      (libsource (lib "eagle-import") (part "CAPACITOR_?_060310V_15PF"))
    )
    (comp (ref "C19")
      (value "CAPACITOR_0603_10V_15PF")
      (footprint "eagle-import:0603-CAP")
      (fields
        (field (name "CAPACITANCE") "15pF")
        (field (name "MANUFACTURER") "Vishay Vitramon")
        (field (name "MPN") "VJ0603A150FXQPW1BC")
        (field (name "TOLERANCE") "1%")
        (field (name "VOLTAGE") "10V")
      )
      (libsource (lib "eagle-import") (part "CAPACITOR_?_060310V_15PF"))
    )
    (comp (ref "D1")
      (value "LED_0603_BLUE")
      (footprint "eagle-import:0603-LED")
      (fields
        (field (name "COLOR") "Blue")
        (field (name "MANUFACTURER") "Kingbright")
        (field (name "MPN") "APT1608VBC/D")
      )
      (libsource (lib "eagle-import") (part "LED_?_0603BLUE"))
    )
    (comp (ref "D2")
      (value "LED_0603_GREEN")
      (footprint "eagle-import:0603-LED")
      (fields
        (field (name "COLOR") "Green")
        (field (name "MANUFACTURER") "Kingbright")
        (field (name "MPN") "APT1608ZGCK")
      )
      (libsource (lib "eagle-import") (part "LED_?_0603GREEN"))
    )
    (comp (ref "D3")
      (value "LED_0603_ORANGE")
      (footprint "eagle-import:0603-LED")
      (fields
        (field (name "COLOR") "Orange")
        (field (name "MANUFACTURER") "Kingbright")
        (field (name "MPN") "APT1608SECK")
      )
      (libsource (lib "eagle-import") (part "LED_?_0603ORANGE"))
    )
    (comp (ref "D4")
      (value "TVS_15V")
      (footprint "eagle-import:SOT-23")
      (fields
        (field (name "MANUFACTURER") "Vishay General Semiconductor - Diodes Division")
        (field (name "MPN") "GSOT15-E3-08")
        (field (name "VOLTAGE") "15V")
      )
      (libsource (lib "eagle-import") (part "TVS_15V"))
    )
    (comp (ref "D101")
      (value "LED_7_SEGMENT_BLUE_DSM7TA")
      (footprint "eagle-import:DSM7T")
      (fields
        (field (name "COLOR") "Blue")
        (field (name "MANUFACTURER") "Visual Communications Company")
        (field (name "MPN") "DSM7TA56106T")
      )
      (libsource (lib "eagle-import") (part "LED_7_SEGMENT_DSM7TABLUE_"))
    )
    (comp (ref "J1")
      (value "JUMPER_0603_")
      (footprint "eagle-import:0603-RES")
      (fields (field (name "MPN") "RC0603FR-130RL") (field (name "MANUFACTURER") "YAGEO"))
      (libsource (lib "eagle-import") (part "JUMPER_?_0603"))
    )
    (comp (ref "J2")
      (value "CONNECTOR-8_μF_S_RA_")
      (footprint "eagle-import:MOLEX_MICROFIT_SMD_RIGHTANGLE_08_DUAL")
      (fields (field (name "MPN") "0430450811") (field (name "MANUFACTURER") "Molex"))
      (libsource (lib "eagle-import") (part "CONNECTOR-8_?_μF_S_RA"))
    )
    (comp (ref "J3")
      (value "CONNECTOR-CAN_μF_S_RA_")
      (footprint "eagle-import:MOLEX_MICROFIT_SMD_RIGHTANGLE_04_DUAL")
      (fields (field (name "MPN") "0430450411") (field (name "MANUFACTURER") "Molex"))
      (libsource (lib "eagle-import") (part "CONNECTOR-CAN_?_μF_S_RA"))
    )
    (comp (ref "J4")
      (value "CONNECTOR-6_μF_S_RA_")
      (footprint "eagle-import:MOLEX_MICROFIT_SMD_RIGHTANGLE_06_DUAL")
      (fields (field (name "MPN") "0430450611") (field (name "MANUFACTURER") "Molex"))
      (libsource (lib "eagle-import") (part "CONNECTOR-6_?_μF_S_RA"))
    )
    (comp (ref "J5")
      (value "CONNECTOR-AVR-ISP_2X05_SMD")
      (footprint "eagle-import:2X05_SMD")
      (fields
        (field (name "MPN") "GBC05DABN-M30")
        (field (name "MANUFACTURER") "Sullins Connector Solutions")
      )
      (libsource (lib "eagle-import") (part "CONNECTOR-AVR-ISP_?2X05_SMD"))
    )
    (comp (ref "L1")
      (value "INDUCTOR_LQM18DH100M70_10UH")
      (footprint "eagle-import:0603-IND")
      (fields
        (field (name "INDUCTANCE") "10µH")
        (field (name "MANUFACTURER") "Murata Electronics")
        (field (name "MPN") "LQM18DH100M70L")
        (field (name "TOLERANCE") "20%")
      )
      (libsource (lib "eagle-import") (part "INDUCTOR_?_LQM18DH100M7010UH"))
    )
    (comp (ref "R3")
      (value "RESISTOR_0603_10K")
      (footprint "eagle-import:0603-RES")
      (fields
        (field (name "MANUFACTURER") "Yageo")
        (field (name "MPN") "RC0603FR-0710KL")
        (field (name "POWER") "0.1W")
        (field (name "RESISTANCE") "10k")
      )
      (libsource (lib "eagle-import") (part "RESISTOR_?_060310K"))
    )
    (comp (ref "R4")
      (value "RESISTOR_0603_60.4")
      (footprint "eagle-import:0603-RES")
      (fields
        (field (name "MANUFACTURER") "Yageo")
        (field (name "MPN") "RC0603FR-0760R4L")
        (field (name "POWER") "0.1W")
        (field (name "RESISTANCE") "60.4")
      )
      (libsource (lib "eagle-import") (part "RESISTOR_?_060360.4"))
    )
    (comp (ref "R6")
      (value "RESISTOR_0603_2.18K")
      (footprint "eagle-import:0603-RES")
      (fields
        (field (name "MANUFACTURER") "YAGEO")
        (field (name "MPN") "RT0805BRD072K18L")
        (field (name "POWER") "0.125W")
        (field (name "RESISTANCE") "2.18k")
      )
      (libsource (lib "eagle-import") (part "RESISTOR_?_06032.18K"))
    )
    (comp (ref "R7")
      (value "RESISTOR_0603_60.4")
      (footprint "eagle-import:0603-RES")
      (fields
        (field (name "MANUFACTURER") "Yageo")
        (field (name "MPN") "RC0603FR-0760R4L")
        (field (name "POWER") "0.1W")
        (field (name "RESISTANCE") "60.4")
      )
      (libsource (lib "eagle-import") (part "RESISTOR_?_060360.4"))
    )
    (comp (ref "R12")
      (value "RESISTOR_0603_10K")
      (footprint "eagle-import:0603-RES")
      (fields
        (field (name "MANUFACTURER") "Yageo")
        (field (name "MPN") "RC0603FR-0710KL")
        (field (name "POWER") "0.1W")
        (field (name "RESISTANCE") "10k")
      )
      (libsource (lib "eagle-import") (part "RESISTOR_?_060310K"))
    )
    (comp (ref "R15")
      (value "RESISTOR_0603_100")
      (footprint "eagle-import:0603-RES")
      (fields
        (field (name "MANUFACTURER") "Yageo")
        (field (name "MPN") "RC0603FR-07100RL")
        (field (name "POWER") "0.1W")
        (field (name "RESISTANCE") "100")
      )
      (libsource (lib "eagle-import") (part "RESISTOR_?_0603100"))
    )
    (comp (ref "RN2")
      (value "RESISTOR_NETWORK_4_160")
      (footprint "eagle-import:1206-RES-ARRAY")
      (fields
        (field (name "MANUFACTURER") "Yageo")
        (field (name "MPN") "YC164-JR-07160RL")
        (field (name "POWER") "1/16W")
        (field (name "RESISTANCE") "160")
      )
      (libsource (lib "eagle-import") (part "RESISTOR_NETWORK_4_160"))
    )
    (comp (ref "RN3")
      (value "RESISTOR_NETWORK_4_1K")
      (footprint "eagle-import:1206-RES-ARRAY")
      (fields
        (field (name "MANUFACTURER") "Yageo")
        (field (name "MPN") "YC164-FR-071KL")
        (field (name "POWER") "1/16W")
        (field (name "RESISTANCE") "1k")
      )
      (libsource (lib "eagle-import") (part "RESISTOR_NETWORK_4_1K"))
    )
    (comp (ref "RN4")
      (value "RESISTOR_NETWORK_4_160")
      (footprint "eagle-import:1206-RES-ARRAY")
      (fields
        (field (name "MANUFACTURER") "Yageo")
        (field (name "MPN") "YC164-JR-07160RL")
        (field (name "POWER") "1/16W")
        (field (name "RESISTANCE") "160")
      )
      (libsource (lib "eagle-import") (part "RESISTOR_NETWORK_4_160"))
    )
    (comp (ref "TP1")
      (value "TEST_POINT")
      (footprint "eagle-import:5015")
      (fields
        (field (name "MPN") "5015")
        (field (name "MANUFACTURER") "Keystone Electronics")
        (field (name "SIGNAL") "+5V")
      )
      (libsource (lib "eagle-import") (part "TEST_POINT"))
    )
    (comp (ref "TP3")
      (value "TEST_POINT")
      (footprint "eagle-import:5015")
      (fields (field (name "MPN") "5015") (field (name "MANUFACTURER") "Keystone Electronics"))
      (libsource (lib "eagle-import") (part "TEST_POINT"))
    )
    (comp (ref "TP5")
      (value "TEST_POINT")
      (footprint "eagle-import:5015")
      (fields (field (name "MPN") "5015") (field (name "MANUFACTURER") "Keystone Electronics"))
      (libsource (lib "eagle-import") (part "TEST_POINT"))
    )
    (comp (ref "U1")
      (value "MCP2515")
      (footprint "eagle-import:TSSOP-20")
      (fields (field (name "MPN") "MCP2515-E/ST") (field (name "MANUFACTURER") "Microchip Technology"))
      (libsource (lib "eagle-import") (part "MCP2515"))
    )
    (comp (ref "U2")
      (value "MCP2562FD")
      (footprint "eagle-import:SOIC-08(NARROW,0.15_)")
      (fields (field (name "MPN") "MCP2562FD-E/SN") (field (name "MANUFACTURER") "Microchip Technology"))
      (libsource (lib "eagle-import") (part "MCP2562FD"))
    )
    (comp (ref "U3")
      (value "MCP23S08")
      (footprint "eagle-import:SSOP-20")
      (fields (field (name "MPN") "MCP23S08-E/SS") (field (name "MANUFACTURER") "Microchip Technology"))
      (libsource (lib "eagle-import") (part "MCP23S08"))
    )
    (comp (ref "U7")
      (value "ATMEGA328P-AU")
      (footprint "eagle-import:TQFP-32")
      (fields (field (name "MPN") "ATMEGA328P-AU") (field (name "MANUFACTURER") "Microchip Technology"))
      (libsource (lib "eagle-import") (part "ATMEGA328P-AU"))
    )
    (comp (ref "X1")
      (value "CRYSTAL_16MHZ")
      (footprint "eagle-import:ECX-42")
      (fields
        (field (name "FREQUENCY") "16 MHz")
        (field (name "MANUFACTURER") "TXC CORPORATION")
        (field (name "MPN") "ECS-160-10-42-CKM-TR")
      )
      (libsource (lib "eagle-import") (part "CRYSTAL_16MHZ"))
    )
    (comp (ref "X2")
      (value "CRYSTAL_16MHZ")
      (footprint "eagle-import:ECX-42")
      (fields
        (field (name "FREQUENCY") "16 MHz")
        (field (name "MANUFACTURER") "TXC CORPORATION")
        (field (name "MPN") "ECS-160-10-42-CKM-TR")
      )
      (libsource (lib "eagle-import") (part "CRYSTAL_16MHZ"))
    )
    (comp (ref "XF1")
      (value "FUSE_HOLDER_MINIBLADESMD")
      (footprint "eagle-import:3588")
      (fields (field (name "MANUFACTURER") "Keystone Electronics") (field (name "MPN") "3588"))
      (libsource (lib "eagle-import") (part "FUSE_HOLDER_SMDMINIBLADE"))
    )
  )
  (nets
    (net (code "1") (name "+12V") (class "Default")
      (node (ref "A1") (pin "2") (pinfunction "IN_2") (pintype "input"))
      (node (ref "C15") (pin "2") (pinfunction "2_2") (pintype "passive"))
      (node (ref "D1") (pin "2") (pinfunction "A_2") (pintype "passive"))
      (node (ref "D4") (pin "3") (pinfunction "C_3") (pintype "passive"))
      (node (ref "J3") (pin "1") (pinfunction "+12V_1") (pintype "power_in"))
      (node (ref "TP3") (pin "1") (pinfunction "1_1") (pintype "passive"))
      (node (ref "U5") (pin "2") (pinfunction "VDD_2") (pintype "power_in"))
      (node (ref "XF1") (pin "3") (pinfunction "2_3") (pintype "passive"))
      (node (ref "XF1") (pin "4") (pinfunction "2_4") (pintype "passive"))
    )
    (net (code "2") (name "BTN_LAUNCH_READ") (class "Default")
      (node (ref "J4") (pin "1") (pinfunction "1_1") (pintype "passive"))
      (node (ref "U7") (pin "26") (pinfunction "17(A3)_26") (pintype "bidirectional"))
    )
    (net (code "3") (name "BTN_MARK_READ") (class "Default")
      (node (ref "J4") (pin "5") (pinfunction "5_5") (pintype "passive"))
      (node (ref "U7") (pin "10") (pinfunction "6(PWM)_10") (pintype "bidirectional"))
    )
    (net (code "4") (name "BTN_MC_CYCLE_READ") (class "Default")
      (node (ref "J4") (pin "4") (pinfunction "4_4") (pintype "passive"))
      (node (ref "U7") (pin "13") (pinfunction "(PWM)9_13") (pintype "bidirectional"))
    )
    (net (code "5") (name "BTN_MODE_READ") (class "Default")
      (node (ref "J4") (pin "3") (pinfunction "3_3") (pintype "passive"))
      (node (ref "U7") (pin "11") (pinfunction "7_11") (pintype "bidirectional"))
    )
    (net (code "6") (name "BTN_START_READ") (class "Default")
      (node (ref "J4") (pin "2") (pinfunction "2_2") (pintype "passive"))
      (node (ref "U7") (pin "25") (pinfunction "16(A2)_25") (pintype "bidirectional"))
    )
    (net (code "7") (name "BUZZER_CTRL") (class "Default")
      (node (ref "R11") (pin "2") (pinfunction "2_2") (pintype "passive"))
      (node (ref "U5") (pin "8") (pinfunction "EN_8") (pintype "input"))
      (node (ref "U7") (pin "27") (pinfunction "18(A4)_27") (pintype "bidirectional"))
    )
    (net (code "8") (name "CANH") (class "Default")
      (node (ref "J2") (pin "4") (pinfunction "4_4") (pintype "passive"))
      (node (ref "J3") (pin "4") (pinfunction "CANH_4") (pintype "bidirectional"))
      (node (ref "U2") (pin "7") (pinfunction "CANH_7") (pintype "bidirectional"))
    )
    (net (code "9") (name "CANL") (class "Default")
      (node (ref "J2") (pin "3") (pinfunction "3_3") (pintype "passive"))
      (node (ref "J3") (pin "3") (pinfunction "CANL_3") (pintype "bidirectional"))
      (node (ref "U2") (pin "6") (pinfunction "CANL_6") (pintype "bidirectional"))
    )
    (net (code "10") (name "GND") (class "Default")
      (node (ref "A1") (pin "11") (pinfunction "GND_11") (pintype "power_in"))
      (node (ref "A1") (pin "3") (pinfunction "GND_3") (pintype "power_in"))
      (node (ref "A1") (pin "7") (pinfunction "GND_7") (pintype "power_in"))
      (node (ref "C1") (pin "2") (pinfunction "2_2") (pintype "passive"))
      (node (ref "C10") (pin "2") (pinfunction "2_2") (pintype "passive"))
      (node (ref "C11") (pin "2") (pinfunction "2_2") (pintype "passive"))
      (node (ref "C12") (pin "2") (pinfunction "2_2") (pintype "passive"))
      (node (ref "C13") (pin "2") (pinfunction "2_2") (pintype "passive"))
      (node (ref "C14") (pin "2") (pinfunction "2_2") (pintype "passive"))
      (node (ref "C15") (pin "1") (pinfunction "1_1") (pintype "passive"))
      (node (ref "C16") (pin "2") (pinfunction "2_2") (pintype "passive"))
      (node (ref "C18") (pin "2") (pinfunction "2_2") (pintype "passive"))
      (node (ref "C19") (pin "2") (pinfunction "2_2") (pintype "passive"))
      (node (ref "C2") (pin "2") (pinfunction "2_2") (pintype "passive"))
      (node (ref "C3") (pin "2") (pinfunction "2_2") (pintype "passive"))
      (node (ref "C4") (pin "2") (pinfunction "2_2") (pintype "passive"))
      (node (ref "C5") (pin "2") (pinfunction "2_2") (pintype "passive"))
      (node (ref "C6") (pin "2") (pinfunction "2_2") (pintype "passive"))
      (node (ref "C7") (pin "2") (pinfunction "2_2") (pintype "passive"))
      (node (ref "C8") (pin "2") (pinfunction "2_2") (pintype "passive"))
      (node (ref "C9") (pin "2") (pinfunction "2_2") (pintype "passive"))
      (node (ref "D4") (pin "1") (pinfunction "A_1") (pintype "passive"))
      (node (ref "DN1") (pin "2") (pinfunction "A_2") (pintype "passive"))
      (node (ref "DN2") (pin "2") (pinfunction "A_2") (pintype "passive"))
      (node (ref "J2") (pin "8") (pinfunction "8_8") (pintype "passive"))
      (node (ref "J3") (pin "2") (pinfunction "GND_2") (pintype "power_in"))
      (node (ref "J4") (pin "6") (pinfunction "6_6") (pintype "passive"))
      (node (ref "J5") (pin "10") (pinfunction "GND_10") (pintype "power_in"))
      (node (ref "J5") (pin "4") (pinfunction "GND_4") (pintype "power_in"))
      (node (ref "J5") (pin "6") (pinfunction "GND_6") (pintype "power_in"))
      (node (ref "J5") (pin "8") (pinfunction "GND_8") (pintype "power_in"))
      (node (ref "Q1") (pin "2") (pinfunction "S_2") (pintype "passive"))
      (node (ref "Q2") (pin "2") (pinfunction "S_2") (pintype "passive"))
      (node (ref "Q3") (pin "2") (pinfunction "S_2") (pintype "passive"))
      (node (ref "Q4") (pin "2") (pinfunction "S_2") (pintype "passive"))
      (node (ref "Q5") (pin "2") (pinfunction "S_2") (pintype "passive"))
      (node (ref "Q6") (pin "2") (pinfunction "S_2") (pintype "passive"))
      (node (ref "Q7") (pin "2") (pinfunction "S_2") (pintype "passive"))
      (node (ref "Q8") (pin "2") (pinfunction "S_2") (pintype "passive"))
      (node (ref "R11") (pin "1") (pinfunction "1_1") (pintype "passive"))
      (node (ref "R21") (pin "2") (pinfunction "2_2") (pintype "passive"))
      (node (ref "R22") (pin "2") (pinfunction "2_2") (pintype "passive"))
      (node (ref "R23") (pin "2") (pinfunction "2_2") (pintype "passive"))
      (node (ref "R24") (pin "2") (pinfunction "2_2") (pintype "passive"))
      (node (ref "R6") (pin "1") (pinfunction "1_1") (pintype "passive"))
      (node (ref "RN3") (pin "3") (pinfunction "1_3") (pintype "passive"))
      (node (ref "RN3") (pin "7") (pinfunction "2_7") (pintype "passive"))
      (node (ref "RN3") (pin "8") (pinfunction "2_8") (pintype "passive"))
      (node (ref "RN5") (pin "1") (pinfunction "1_1") (pintype "passive"))
      (node (ref "RN5") (pin "2") (pinfunction "1_2") (pintype "passive"))
      (node (ref "RN5") (pin "3") (pinfunction "1_3") (pintype "passive"))
      (node (ref "RN5") (pin "4") (pinfunction "1_4") (pintype "passive"))
      (node (ref "RN7") (pin "1") (pinfunction "1_1") (pintype "passive"))
      (node (ref "RN7") (pin "2") (pinfunction "1_2") (pintype "passive"))
      (node (ref "RN7") (pin "3") (pinfunction "1_3") (pintype "passive"))
      (node (ref "RN7") (pin "4") (pinfunction "1_4") (pintype "passive"))
      (node (ref "TP5") (pin "1") (pinfunction "1_1") (pintype "passive"))
      (node (ref "U1") (pin "10") (pinfunction "GND_10") (pintype "power_in"))
      (node (ref "U2") (pin "2") (pinfunction "GND_2") (pintype "power_in"))
      (node (ref "U2") (pin "8") (pinfunction "STBY_8") (pintype "passive"))
      (node (ref "U3") (pin "4") (pinfunction "1_4") (pintype "input"))
      (node (ref "U3") (pin "5") (pinfunction "2_5") (pintype "input"))
      (node (ref "U3") (pin "9") (pinfunction "GND_9") (pintype "power_in"))
      (node (ref "U4") (pin "3") (pinfunction "GND_3") (pintype "power_in"))
      (node (ref "U5") (pin "5") (pinfunction "GND_5") (pintype "power_in"))
      (node (ref "U6") (pin "3") (pinfunction "GND_3") (pintype "power_in"))
      (node (ref "U7") (pin "21") (pinfunction "GND_21") (pintype "power_in"))
      (node (ref "U7") (pin "3") (pinfunction "GND_3") (pintype "power_in"))
      (node (ref "U7") (pin "5") (pinfunction "GND_5") (pintype "power_in"))
      (node (ref "X1") (pin "2") (pinfunction "GND_2") (pintype "power_in"))
      (node (ref "X1") (pin "4") (pinfunction "GND_4") (pintype "power_in"))
      (node (ref "X2") (pin "2") (pinfunction "GND_2") (pintype "power_in"))
      (node (ref "X2") (pin "4") (pinfunction "GND_4") (pintype "power_in"))
    )
    (net (code "11") (name "LED_AMS_CTRL") (class "Default")
      (node (ref "DN2") (pin "6") (pinfunction "C_6") (pintype "passive"))
      (node (ref "RN1") (pin "1") (pinfunction "1_1") (pintype "passive"))
      (node (ref "RN5") (pin "7") (pinfunction "2_7") (pintype "passive"))
      (node (ref "U7") (pin "30") (pinfunction "0_30") (pintype "bidirectional"))
    )
    (net (code "12") (name "LED_IMD_CTRL") (class "Default")
      (node (ref "DN2") (pin "4") (pinfunction "C_4") (pintype "passive"))
      (node (ref "RN6") (pin "4") (pinfunction "1_4") (pintype "passive"))
      (node (ref "RN7") (pin "8") (pinfunction "2_8") (pintype "passive"))
      (node (ref "U7") (pin "31") (pinfunction "1_31") (pintype "bidirectional"))
    )
    (net (code "13") (name "LED_MC_ERR_CTRL") (class "Default")
      (node (ref "DN2") (pin "3") (pinfunction "C_3") (pintype "passive"))
      (node (ref "RN6") (pin "1") (pinfunction "1_1") (pintype "passive"))
      (node (ref "RN7") (pin "6") (pinfunction "2_6") (pintype "passive"))
      (node (ref "U7") (pin "1") (pinfunction "3(PWM)_1") (pintype "bidirectional"))
    )
    (net (code "14") (name "LED_MODE_CTRL") (class "Default")
      (node (ref "DN2") (pin "5") (pinfunction "C_5") (pintype "passive"))
      (node (ref "RN6") (pin "3") (pinfunction "1_3") (pintype "passive"))
      (node (ref "RN7") (pin "7") (pinfunction "2_7") (pintype "passive"))
      (node (ref "U7") (pin "32") (pinfunction "2_32") (pintype "bidirectional"))
    )
    (net (code "15") (name "LED_START_CTRL") (class "Default")
      (node (ref "DN2") (pin "1") (pinfunction "C_1") (pintype "passive"))
      (node (ref "RN6") (pin "2") (pinfunction "1_2") (pintype "passive"))
      (node (ref "RN7") (pin "5") (pinfunction "2_5") (pintype "passive"))
      (node (ref "U7") (pin "2") (pinfunction "4_2") (pintype "bidirectional"))
    )
    (net (code "16") (name "Net-(A1-TRIM)") (class "Default")
      (node (ref "A1") (pin "6") (pinfunction "TRIM_6") (pintype "passive"))
      (node (ref "R6") (pin "2") (pinfunction "2_2") (pintype "passive"))
    )
    (net (code "17") (name "Net-(C7-Pad1)") (class "Default")
      (node (ref "C7") (pin "1") (pinfunction "1_1") (pintype "passive"))
      (node (ref "R4") (pin "1") (pinfunction "1_1") (pintype "passive"))
      (node (ref "R7") (pin "1") (pinfunction "1_1") (pintype "passive"))
    )
    (net (code "18") (name "Net-(D1-C)") (class "Default")
      (node (ref "D1") (pin "1") (pinfunction "C_1") (pintype "passive"))
      (node (ref "RN3") (pin "2") (pinfunction "1_2") (pintype "passive"))
    )
    (net (code "19") (name "Net-(D2-C)") (class "Default")
      (node (ref "D2") (pin "1") (pinfunction "C_1") (pintype "passive"))
      (node (ref "RN3") (pin "1") (pinfunction "1_1") (pintype "passive"))
    )
    (net (code "20") (name "Net-(D3-A)") (class "Default")
      (node (ref "D3") (pin "2") (pinfunction "A_2") (pintype "passive"))
      (node (ref "U7") (pin "23") (pinfunction "14(A0)_23") (pintype "bidirectional"))
    )
    (net (code "21") (name "Net-(D3-C)") (class "Default")
      (node (ref "D3") (pin "1") (pinfunction "C_1") (pintype "passive"))
      (node (ref "RN3") (pin "6") (pinfunction "2_6") (pintype "passive"))
    )
    (net (code "22") (name "Net-(D100-PadC)") (class "Default")
      (node (ref "D100") (pin "C") (pinfunction "C_C") (pintype "passive"))
      (node (ref "R1") (pin "1") (pinfunction "1_1") (pintype "passive"))
    )
    (net (code "23") (name "Net-(D101-A)") (class "Default")
      (node (ref "D101") (pin "7") (pinfunction "A_7") (pintype "input"))
      (node (ref "RN2") (pin "8") (pinfunction "2_8") (pintype "passive"))
    )
    (net (code "24") (name "Net-(D101-B)") (class "Default")
      (node (ref "D101") (pin "6") (pinfunction "B_6") (pintype "input"))
      (node (ref "RN2") (pin "7") (pinfunction "2_7") (pintype "passive"))
    )
    (net (code "25") (name "Net-(D101-C)") (class "Default")
      (node (ref "D101") (pin "4") (pinfunction "C_4") (pintype "input"))
      (node (ref "RN2") (pin "6") (pinfunction "2_6") (pintype "passive"))
    )
    (net (code "26") (name "Net-(D101-D)") (class "Default")
      (node (ref "D101") (pin "2") (pinfunction "D_2") (pintype "input"))
      (node (ref "RN2") (pin "5") (pinfunction "2_5") (pintype "passive"))
    )
    (net (code "27") (name "Net-(D101-E)") (class "Default")
      (node (ref "D101") (pin "1") (pinfunction "E_1") (pintype "input"))
      (node (ref "RN4") (pin "8") (pinfunction "2_8") (pintype "passive"))
    )
    (net (code "28") (name "Net-(D101-F)") (class "Default")
      (node (ref "D101") (pin "9") (pinfunction "F_9") (pintype "input"))
      (node (ref "RN4") (pin "7") (pinfunction "2_7") (pintype "passive"))
    )
    (net (code "29") (name "Net-(D101-G)") (class "Default")
      (node (ref "D101") (pin "10") (pinfunction "G_10") (pintype "input"))
      (node (ref "RN4") (pin "6") (pinfunction "2_6") (pintype "passive"))
    )
    (net (code "30") (name "Net-(D102-PadC)") (class "Default")
      (node (ref "D102") (pin "C") (pinfunction "C_C") (pintype "passive"))
      (node (ref "R25") (pin "1") (pinfunction "1_1") (pintype "passive"))
    )
    (net (code "31") (name "Net-(D103-PadC)") (class "Default")
      (node (ref "D103") (pin "C") (pinfunction "C_C") (pintype "passive"))
      (node (ref "R2") (pin "1") (pinfunction "1_1") (pintype "passive"))
    )
    (net (code "32") (name "Net-(D104-PadC)") (class "Default")
      (node (ref "D104") (pin "C") (pinfunction "C_C") (pintype "passive"))
      (node (ref "R8") (pin "1") (pinfunction "1_1") (pintype "passive"))
    )
    (net (code "33") (name "Net-(D105-PadC)") (class "Default")
      (node (ref "D105") (pin "C") (pinfunction "C_C") (pintype "passive"))
      (node (ref "R5") (pin "1") (pinfunction "1_1") (pintype "passive"))
    )
    (net (code "34") (name "Net-(D106-PadC)") (class "Default")
      (node (ref "D106") (pin "C") (pinfunction "C_C") (pintype "passive"))
      (node (ref "R14") (pin "1") (pinfunction "1_1") (pintype "passive"))
    )
    (net (code "35") (name "Net-(D107-PadC)") (class "Default")
      (node (ref "D107") (pin "C") (pinfunction "C_C") (pintype "passive"))
      (node (ref "R20") (pin "1") (pinfunction "1_1") (pintype "passive"))
    )
    (net (code "36") (name "Net-(D108-PadC)") (class "Default")
      (node (ref "D108") (pin "C") (pinfunction "C_C") (pintype "passive"))
      (node (ref "R10") (pin "1") (pinfunction "1_1") (pintype "passive"))
    )
    (net (code "37") (name "Net-(DN1A-C)") (class "Default")
      (node (ref "DN1") (pin "1") (pinfunction "C_1") (pintype "passive"))
      (node (ref "RN1") (pin "2") (pinfunction "1_2") (pintype "passive"))
      (node (ref "RN5") (pin "8") (pinfunction "2_8") (pintype "passive"))
      (node (ref "U4") (pin "4") (pinfunction "~{IN}_4") (pintype "output"))
    )
    (net (code "38") (name "Net-(DN1C-C)") (class "Default")
      (node (ref "DN1") (pin "4") (pinfunction "C_4") (pintype "passive"))
      (node (ref "RN1") (pin "4") (pinfunction "1_4") (pintype "passive"))
      (node (ref "RN5") (pin "5") (pinfunction "2_5") (pintype "passive"))
      (node (ref "U6") (pin "4") (pinfunction "~{IN}_4") (pintype "output"))
    )
    (net (code "39") (name "Net-(J1-Pad1)") (class "Default")
      (node (ref "J1") (pin "1") (pinfunction "1_1") (pintype "passive"))
      (node (ref "R4") (pin "2") (pinfunction "2_2") (pintype "passive"))
    )
    (net (code "40") (name "Net-(J2-Pad1)") (class "Default")
      (node (ref "J2") (pin "1") (pinfunction "1_1") (pintype "passive"))
      (node (ref "XF1") (pin "1") (pinfunction "1_1") (pintype "passive"))
      (node (ref "XF1") (pin "2") (pinfunction "1_2") (pintype "passive"))
    )
    (net (code "41") (name "Net-(J5-CIPO)") (class "Default")
      (node (ref "J5") (pin "9") (pinfunction "CIPO_9") (pintype "bidirectional"))
      (node (ref "U1") (pin "17") (pinfunction "SDO_17") (pintype "output"))
      (node (ref "U3") (pin "3") (pinfunction "SDO_3") (pintype "output"))
      (node (ref "U7") (pin "16") (pinfunction "(CIPO)12_16") (pintype "bidirectional"))
    )
    (net (code "42") (name "Net-(J5-CLK)") (class "Default")
      (node (ref "J5") (pin "7") (pinfunction "CLK_7") (pintype "bidirectional"))
      (node (ref "U1") (pin "14") (pinfunction "CLK_14") (pintype "input"))
      (node (ref "U3") (pin "1") (pinfunction "CLK_1") (pintype "input"))
      (node (ref "U7") (pin "17") (pinfunction "(CLK)13_17") (pintype "bidirectional"))
    )
    (net (code "43") (name "Net-(J5-COPI)") (class "Default")
      (node (ref "J5") (pin "1") (pinfunction "COPI_1") (pintype "bidirectional"))
      (node (ref "U1") (pin "16") (pinfunction "SDI_16") (pintype "input"))
      (node (ref "U3") (pin "2") (pinfunction "SDI_2") (pintype "input"))
      (node (ref "U7") (pin "15") (pinfunction "(PWM/COPI)11_15") (pintype "bidirectional"))
    )
    (net (code "44") (name "Net-(LS100-FEEDBACK)") (class "Default")
      (node (ref "LS100") (pin "F") (pinfunction "FEEDBACK_F") (pintype "bidirectional"))
      (node (ref "R9") (pin "2") (pinfunction "2_2") (pintype "passive"))
    )
    (net (code "45") (name "Net-(LS100-GND)") (class "Default")
      (node (ref "LS100") (pin "G") (pinfunction "GND_G") (pintype "power_in"))
      (node (ref "R13") (pin "1") (pinfunction "1_1") (pintype "passive"))
      (node (ref "U5") (pin "6") (pinfunction "HORNB_6") (pintype "output"))
    )
    (net (code "46") (name "Net-(LS100-MAIN)") (class "Default")
      (node (ref "C17") (pin "1") (pinfunction "1_1") (pintype "passive"))
      (node (ref "LS100") (pin "M") (pinfunction "MAIN_M") (pintype "power_in"))
      (node (ref "U5") (pin "7") (pinfunction "HORNS_7") (pintype "output"))
    )
    (net (code "47") (name "Net-(Q1-D)") (class "Default")
      (node (ref "Q1") (pin "3") (pinfunction "D_3") (pintype "passive"))
      (node (ref "R1") (pin "2") (pinfunction "2_2") (pintype "passive"))
    )
    (net (code "48") (name "Net-(Q1-G)") (class "Default")
      (node (ref "Q1") (pin "1") (pinfunction "G_1") (pintype "passive"))
      (node (ref "RN1") (pin "8") (pinfunction "2_8") (pintype "passive"))
    )
    (net (code "49") (name "Net-(Q2-D)") (class "Default")
      (node (ref "Q2") (pin "3") (pinfunction "D_3") (pintype "passive"))
      (node (ref "R2") (pin "2") (pinfunction "2_2") (pintype "passive"))
    )
    (net (code "50") (name "Net-(Q2-G)") (class "Default")
      (node (ref "Q2") (pin "1") (pinfunction "G_1") (pintype "passive"))
      (node (ref "RN1") (pin "5") (pinfunction "2_5") (pintype "passive"))
    )
    (net (code "51") (name "Net-(Q3-D)") (class "Default")
      (node (ref "Q3") (pin "3") (pinfunction "D_3") (pintype "passive"))
      (node (ref "R5") (pin "2") (pinfunction "2_2") (pintype "passive"))
    )
    (net (code "52") (name "Net-(Q3-G)") (class "Default")
      (node (ref "Q3") (pin "1") (pinfunction "G_1") (pintype "passive"))
      (node (ref "RN1") (pin "6") (pinfunction "2_6") (pintype "passive"))
    )
    (net (code "53") (name "Net-(Q4-D)") (class "Default")
      (node (ref "Q4") (pin "3") (pinfunction "D_3") (pintype "passive"))
      (node (ref "R8") (pin "2") (pinfunction "2_2") (pintype "passive"))
    )
    (net (code "54") (name "Net-(Q4-G)") (class "Default")
      (node (ref "Q4") (pin "1") (pinfunction "G_1") (pintype "passive"))
      (node (ref "RN1") (pin "7") (pinfunction "2_7") (pintype "passive"))
    )
    (net (code "55") (name "Net-(Q5-D)") (class "Default")
      (node (ref "Q5") (pin "3") (pinfunction "D_3") (pintype "passive"))
      (node (ref "R10") (pin "2") (pinfunction "2_2") (pintype "passive"))
    )
    (net (code "56") (name "Net-(Q5-G)") (class "Default")
      (node (ref "Q5") (pin "1") (pinfunction "G_1") (pintype "passive"))
      (node (ref "RN6") (pin "5") (pinfunction "2_5") (pintype "passive"))
    )
    (net (code "57") (name "Net-(Q6-D)") (class "Default")
      (node (ref "Q6") (pin "3") (pinfunction "D_3") (pintype "passive"))
      (node (ref "R14") (pin "2") (pinfunction "2_2") (pintype "passive"))
    )
    (net (code "58") (name "Net-(Q6-G)") (class "Default")
      (node (ref "Q6") (pin "1") (pinfunction "G_1") (pintype "passive"))
      (node (ref "RN6") (pin "6") (pinfunction "2_6") (pintype "passive"))
    )
    (net (code "59") (name "Net-(Q7-D)") (class "Default")
      (node (ref "Q7") (pin "3") (pinfunction "D_3") (pintype "passive"))
      (node (ref "R20") (pin "2") (pinfunction "2_2") (pintype "passive"))
    )
    (net (code "60") (name "Net-(Q7-G)") (class "Default")
      (node (ref "Q7") (pin "1") (pinfunction "G_1") (pintype "passive"))
      (node (ref "RN6") (pin "7") (pinfunction "2_7") (pintype "passive"))
    )
    (net (code "61") (name "Net-(Q8-D)") (class "Default")
      (node (ref "Q8") (pin "3") (pinfunction "D_3") (pintype "passive"))
      (node (ref "R25") (pin "2") (pinfunction "2_2") (pintype "passive"))
    )
    (net (code "62") (name "Net-(Q8-G)") (class "Default")
      (node (ref "Q8") (pin "1") (pinfunction "G_1") (pintype "passive"))
      (node (ref "RN6") (pin "8") (pinfunction "2_8") (pintype "passive"))
    )
    (net (code "63") (name "Net-(RN2B-1)") (class "Default")
      (node (ref "RN2") (pin "2") (pinfunction "1_2") (pintype "passive"))
      (node (ref "U3") (pin "13") (pinfunction "GPA1_13") (pintype "bidirectional"))
    )
    (net (code "64") (name "Net-(RN2C-1)") (class "Default")
      (node (ref "RN2") (pin "3") (pinfunction "1_3") (pintype "passive"))
      (node (ref "U3") (pin "14") (pinfunction "GPA2_14") (pintype "bidirectional"))
    )
    (net (code "65") (name "Net-(RN2D-1)") (class "Default")
      (node (ref "RN2") (pin "4") (pinfunction "1_4") (pintype "passive"))
      (node (ref "U3") (pin "15") (pinfunction "GPA3_15") (pintype "bidirectional"))
    )
    (net (code "66") (name "Net-(RN4B-1)") (class "Default")
      (node (ref "RN4") (pin "2") (pinfunction "1_2") (pintype "passive"))
      (node (ref "U3") (pin "17") (pinfunction "GPA5_17") (pintype "bidirectional"))
    )
    (net (code "67") (name "Net-(RN4C-1)") (class "Default")
      (node (ref "RN4") (pin "3") (pinfunction "1_3") (pintype "passive"))
      (node (ref "U3") (pin "18") (pinfunction "GPA6_18") (pintype "bidirectional"))
    )
    (net (code "68") (name "Net-(U1-OSC1)") (class "Default")
      (node (ref "C2") (pin "1") (pinfunction "1_1") (pintype "passive"))
      (node (ref "U1") (pin "9") (pinfunction "OSC1_9") (pintype "bidirectional"))
      (node (ref "X1") (pin "1") (pinfunction "1_1") (pintype "passive"))
    )
    (net (code "69") (name "Net-(U1-OSC2)") (class "Default")
      (node (ref "C1") (pin "1") (pinfunction "1_1") (pintype "passive"))
      (node (ref "U1") (pin "8") (pinfunction "OSC2_8") (pintype "bidirectional"))
      (node (ref "X1") (pin "3") (pinfunction "3_3") (pintype "passive"))
    )
    (net (code "70") (name "Net-(U1-RX)") (class "Default")
      (node (ref "J1") (pin "2") (pinfunction "2_2") (pintype "passive"))
      (node (ref "U1") (pin "2") (pinfunction "RX_2") (pintype "input"))
      (node (ref "U2") (pin "4") (pinfunction "RXD_4") (pintype "output"))
    )
    (net (code "71") (name "Net-(U1-TX)") (class "Default")
      (node (ref "R7") (pin "2") (pinfunction "2_2") (pintype "passive"))
      (node (ref "U1") (pin "1") (pinfunction "TX_1") (pintype "output"))
      (node (ref "U2") (pin "1") (pinfunction "TXD_1") (pintype "input"))
    )
    (net (code "72") (name "Net-(U1-~{CS})") (class "Default")
      (node (ref "U1") (pin "18") (pinfunction "~{CS}_18") (pintype "input"))
      (node (ref "U7") (pin "14") (pinfunction "(PWM/CS)10_14") (pintype "bidirectional"))
    )
    (net (code "73") (name "Net-(U1-~{RESET})") (class "Default")
      (node (ref "R3") (pin "2") (pinfunction "2_2") (pintype "passive"))
      (node (ref "U1") (pin "19") (pinfunction "~{RESET}_19") (pintype "input"))
    )
    (net (code "74") (name "Net-(U3-GPA0)") (class "Default")
      (node (ref "RN2") (pin "1") (pinfunction "1_1") (pintype "passive"))
      (node (ref "U3") (pin "12") (pinfunction "GPA0_12") (pintype "bidirectional"))
    )
    (net (code "75") (name "Net-(U3-GPA4)") (class "Default")
      (node (ref "RN4") (pin "1") (pinfunction "1_1") (pintype "passive"))
      (node (ref "U3") (pin "16") (pinfunction "GPA4_16") (pintype "bidirectional"))
    )
    (net (code "76") (name "Net-(U3-~{CS})") (class "Default")
      (node (ref "R15") (pin "2") (pinfunction "2_2") (pintype "passive"))
      (node (ref "U3") (pin "7") (pinfunction "~{CS}_7") (pintype "input"))
    )
    (net (code "77") (name "Net-(U5-FEED)") (class "Default")
      (node (ref "C17") (pin "2") (pinfunction "2_2") (pintype "passive"))
      (node (ref "R13") (pin "2") (pinfunction "2_2") (pintype "passive"))
      (node (ref "R9") (pin "1") (pinfunction "1_1") (pintype "passive"))
      (node (ref "U5") (pin "4") (pinfunction "FEED_4") (pintype "input"))
    )
    (net (code "78") (name "Net-(U7-(XTAL1)14)") (class "Default")
      (node (ref "C18") (pin "1") (pinfunction "1_1") (pintype "passive"))
      (node (ref "U7") (pin "7") (pinfunction "(XTAL1)14_7") (pintype "bidirectional"))
      (node (ref "X2") (pin "1") (pinfunction "1_1") (pintype "passive"))
    )
    (net (code "79") (name "Net-(U7-(XTAL2)15)") (class "Default")
      (node (ref "C19") (pin "1") (pinfunction "1_1") (pintype "passive"))
      (node (ref "U7") (pin "8") (pinfunction "(XTAL2)15_8") (pintype "bidirectional"))
      (node (ref "X2") (pin "3") (pinfunction "3_3") (pintype "passive"))
    )
    (net (code "80") (name "Net-(U7-8)") (class "Default")
      (node (ref "R15") (pin "1") (pinfunction "1_1") (pintype "passive"))
      (node (ref "U7") (pin "12") (pinfunction "8_12") (pintype "bidirectional"))
    )
    (net (code "81") (name "Net-(U7-AREF)") (class "Default")
      (node (ref "C13") (pin "1") (pinfunction "1_1") (pintype "passive"))
      (node (ref "U7") (pin "20") (pinfunction "AREF_20") (pintype "input"))
    )
    (net (code "82") (name "Net-(U7-AVDD)") (class "Default")
      (node (ref "C14") (pin "1") (pinfunction "1_1") (pintype "passive"))
      (node (ref "L1") (pin "1") (pinfunction "1_1") (pintype "passive"))
      (node (ref "U7") (pin "18") (pinfunction "AVDD_18") (pintype "power_in"))
    )
    (net (code "83") (name "RESET") (class "Default")
      (node (ref "J5") (pin "5") (pinfunction "RESET_5") (pintype "output"))
      (node (ref "R12") (pin "2") (pinfunction "2_2") (pintype "passive"))
      (node (ref "U7") (pin "29") (pinfunction "22(~{RESET})_29") (pintype "bidirectional"))
    )
    (net (code "84") (name "SHUTDOWN_F") (class "Default")
      (node (ref "J2") (pin "7") (pinfunction "7_7") (pintype "passive"))
      (node (ref "R19") (pin "1") (pinfunction "1_1") (pintype "passive"))
      (node (ref "TP2") (pin "1") (pinfunction "1_1") (pintype "passive"))
    )
    (net (code "85") (name "SHUTDOWN_F_READ") (class "Default")
      (node (ref "DN1") (pin "3") (pinfunction "C_3") (pintype "passive"))
      (node (ref "R19") (pin "2") (pinfunction "2_2") (pintype "passive"))
      (node (ref "R23") (pin "1") (pinfunction "1_1") (pintype "passive"))
      (node (ref "RN1") (pin "3") (pinfunction "1_3") (pintype "passive"))
      (node (ref "RN5") (pin "6") (pinfunction "2_6") (pintype "passive"))
      (node (ref "U7") (pin "19") (pinfunction "A6_19") (pintype "bidirectional"))
    )
    (net (code "86") (name "SHUTDOWN_G") (class "Default")
      (node (ref "J2") (pin "6") (pinfunction "6_6") (pintype "passive"))
      (node (ref "R18") (pin "1") (pinfunction "1_1") (pintype "passive"))
      (node (ref "TP4") (pin "1") (pinfunction "1_1") (pintype "passive"))
    )
    (net (code "87") (name "SHUTDOWN_G_READ") (class "Default")
      (node (ref "R18") (pin "2") (pinfunction "2_2") (pintype "passive"))
      (node (ref "R22") (pin "1") (pinfunction "1_1") (pintype "passive"))
      (node (ref "U4") (pin "2") (pinfunction "IN_2") (pintype "input"))
      (node (ref "U7") (pin "24") (pinfunction "15(A1)_24") (pintype "bidirectional"))
    )
    (net (code "88") (name "SHUTDOWN_H") (class "Default")
      (node (ref "J2") (pin "5") (pinfunction "5_5") (pintype "passive"))
      (node (ref "R17") (pin "1") (pinfunction "1_1") (pintype "passive"))
      (node (ref "TP6") (pin "1") (pinfunction "1_1") (pintype "passive"))
    )
    (net (code "89") (name "SHUTDOWN_H_READ") (class "Default")
      (node (ref "R17") (pin "2") (pinfunction "2_2") (pintype "passive"))
      (node (ref "R21") (pin "1") (pinfunction "1_1") (pintype "passive"))
      (node (ref "U7") (pin "22") (pinfunction "A7_22") (pintype "bidirectional"))
    )
    (net (code "90") (name "SHUTDOWN_I") (class "Default")
      (node (ref "J2") (pin "2") (pinfunction "2_2") (pintype "passive"))
      (node (ref "R16") (pin "1") (pinfunction "1_1") (pintype "passive"))
      (node (ref "TP7") (pin "1") (pinfunction "1_1") (pintype "passive"))
    )
    (net (code "91") (name "SHUTDOWN_I_READ") (class "Default")
      (node (ref "R16") (pin "2") (pinfunction "2_2") (pintype "passive"))
      (node (ref "R24") (pin "1") (pinfunction "1_1") (pintype "passive"))
      (node (ref "U6") (pin "2") (pinfunction "IN_2") (pintype "input"))
      (node (ref "U7") (pin "9") (pinfunction "5(PWM)_9") (pintype "bidirectional"))
    )
    (net (code "92") (name "VDD") (class "Default")
      (node (ref "A1") (pin "4") (pinfunction "OUT_4") (pintype "power_in"))
      (node (ref "C10") (pin "1") (pinfunction "1_1") (pintype "passive"))
      (node (ref "C11") (pin "1") (pinfunction "1_1") (pintype "passive"))
      (node (ref "C12") (pin "1") (pinfunction "1_1") (pintype "passive"))
      (node (ref "C16") (pin "1") (pinfunction "1_1") (pintype "passive"))
      (node (ref "C3") (pin "1") (pinfunction "1_1") (pintype "passive"))
      (node (ref "C4") (pin "1") (pinfunction "1_1") (pintype "passive"))
      (node (ref "C5") (pin "1") (pinfunction "1_1") (pintype "passive"))
      (node (ref "C6") (pin "1") (pinfunction "1_1") (pintype "passive"))
      (node (ref "C8") (pin "1") (pinfunction "1_1") (pintype "passive"))
      (node (ref "C9") (pin "1") (pinfunction "1_1") (pintype "passive"))
      (node (ref "D100") (pin "A") (pinfunction "A_A") (pintype "passive"))
      (node (ref "D101") (pin "3") (pinfunction "VDD_3") (pintype "power_in"))
      (node (ref "D101") (pin "8") (pinfunction "VDD_8") (pintype "power_in"))
      (node (ref "D102") (pin "A") (pinfunction "A_A") (pintype "passive"))
      (node (ref "D103") (pin "A") (pinfunction "A_A") (pintype "passive"))
      (node (ref "D104") (pin "A") (pinfunction "A_A") (pintype "passive"))
      (node (ref "D105") (pin "A") (pinfunction "A_A") (pintype "passive"))
      (node (ref "D106") (pin "A") (pinfunction "A_A") (pintype "passive"))
      (node (ref "D107") (pin "A") (pinfunction "A_A") (pintype "passive"))
      (node (ref "D108") (pin "A") (pinfunction "A_A") (pintype "passive"))
      (node (ref "D2") (pin "2") (pinfunction "A_2") (pintype "passive"))
      (node (ref "J5") (pin "2") (pinfunction "+5V_2") (pintype "power_in"))
      (node (ref "L1") (pin "2") (pinfunction "2_2") (pintype "passive"))
      (node (ref "R12") (pin "1") (pinfunction "1_1") (pintype "passive"))
      (node (ref "R3") (pin "1") (pinfunction "1_1") (pintype "passive"))
      (node (ref "TP1") (pin "1") (pinfunction "1_1") (pintype "passive"))
      (node (ref "U1") (pin "20") (pinfunction "VDD_20") (pintype "power_in"))
      (node (ref "U2") (pin "3") (pinfunction "VDD_3") (pintype "power_in"))
      (node (ref "U2") (pin "5") (pinfunction "VIO_5") (pintype "power_in"))
      (node (ref "U3") (pin "20") (pinfunction "VDD_20") (pintype "power_in"))
      (node (ref "U3") (pin "6") (pinfunction "~{RESET}_6") (pintype "input"))
      (node (ref "U4") (pin "5") (pinfunction "VDD_5") (pintype "power_in"))
      (node (ref "U6") (pin "5") (pinfunction "VDD_5") (pintype "power_in"))
      (node (ref "U7") (pin "4") (pinfunction "VDD_4") (pintype "power_in"))
      (node (ref "U7") (pin "6") (pinfunction "VDD_6") (pintype "power_in"))
    )
    (net (code "93") (name "unconnected-(A1-EN-Pad1)") (class "Default")
      (node (ref "A1") (pin "1") (pinfunction "EN_1") (pintype "input"))
    )
    (net (code "94") (name "unconnected-(U1-CLKOUT-Pad3)") (class "Default")
      (node (ref "U1") (pin "3") (pinfunction "CLKOUT_3") (pintype "output"))
    )
    (net (code "95") (name "unconnected-(U1-~{INT}-Pad13)") (class "Default")
      (node (ref "U1") (pin "13") (pinfunction "~{INT}_13") (pintype "output"))
    )
    (net (code "96") (name "unconnected-(U1-~{RX0BF}-Pad12)") (class "Default")
      (node (ref "U1") (pin "12") (pinfunction "~{RX0BF}_12") (pintype "output"))
    )
    (net (code "97") (name "unconnected-(U1-~{RX1BF}-Pad11)") (class "Default")
      (node (ref "U1") (pin "11") (pinfunction "~{RX1BF}_11") (pintype "output"))
    )
    (net (code "98") (name "unconnected-(U1-~{TX0RTS}-Pad4)") (class "Default")
      (node (ref "U1") (pin "4") (pinfunction "~{TX0RTS}_4") (pintype "input"))
    )
    (net (code "99") (name "unconnected-(U1-~{TX1RTS}-Pad5)") (class "Default")
      (node (ref "U1") (pin "5") (pinfunction "~{TX1RTS}_5") (pintype "input"))
    )
    (net (code "100") (name "unconnected-(U1-~{TX2RTS}-Pad7)") (class "Default")
      (node (ref "U1") (pin "7") (pinfunction "~{TX2RTS}_7") (pintype "input"))
    )
    (net (code "101") (name "unconnected-(U3-GPA7-Pad19)") (class "Default")
      (node (ref "U3") (pin "19") (pinfunction "GPA7_19") (pintype "bidirectional"))
    )
    (net (code "102") (name "unconnected-(U3-INT-Pad8)") (class "Default")
      (node (ref "U3") (pin "8") (pinfunction "INT_8") (pintype "output"))
    )
    (net (code "103") (name "unconnected-(U7-19(A5)-Pad28)") (class "Default")
      (node (ref "U7") (pin "28") (pinfunction "19(A5)_28") (pintype "bidirectional"))
    )
  )
)
